# breakout.net
KiCad netlist of a schematic drawn in EAGLE
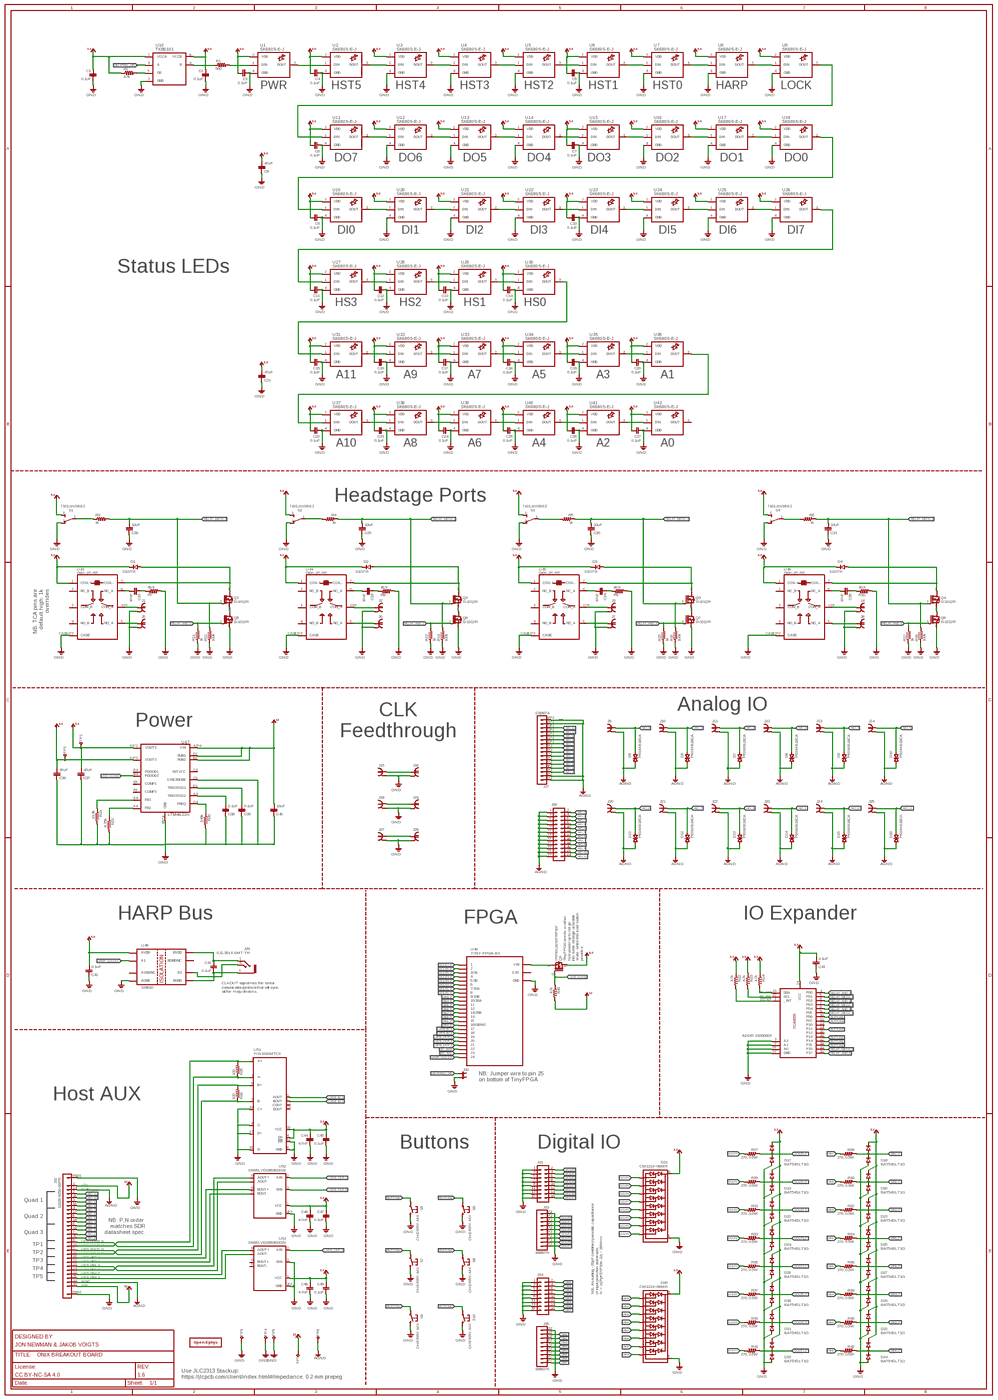
[diagram p0: schematic, sheet 1, overview]
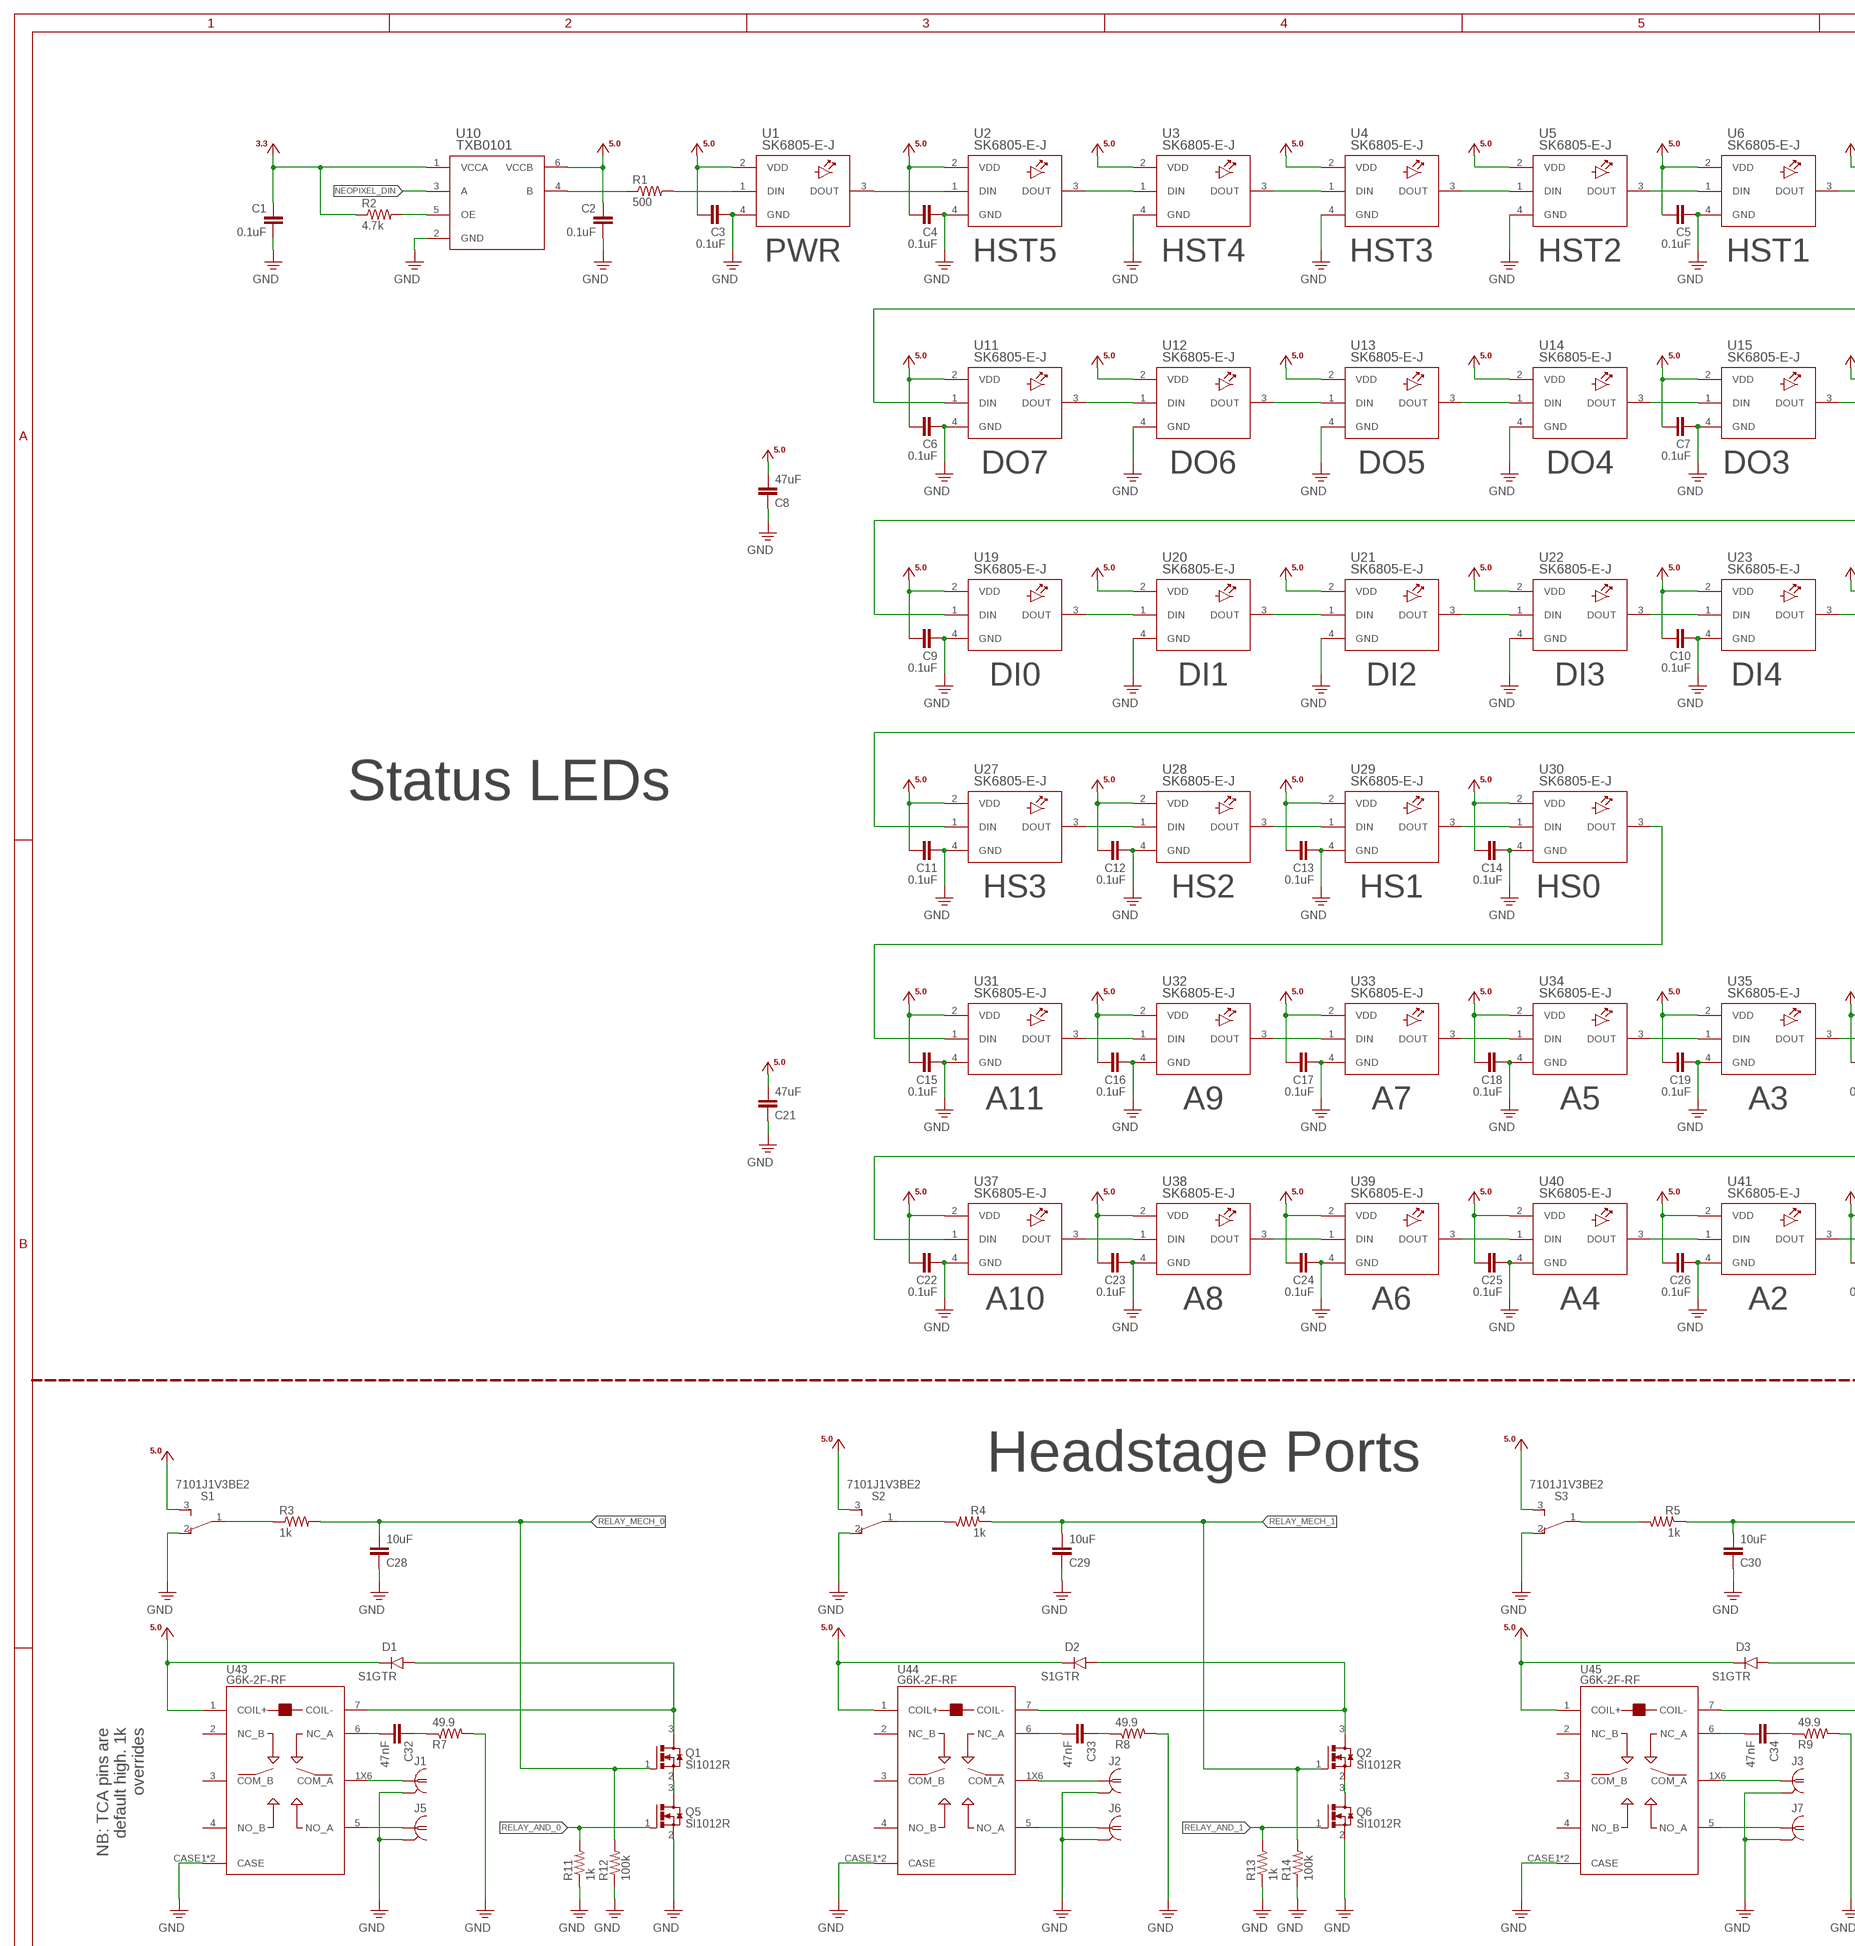
[diagram p1: schematic, sheet 1, part 1 of 4]
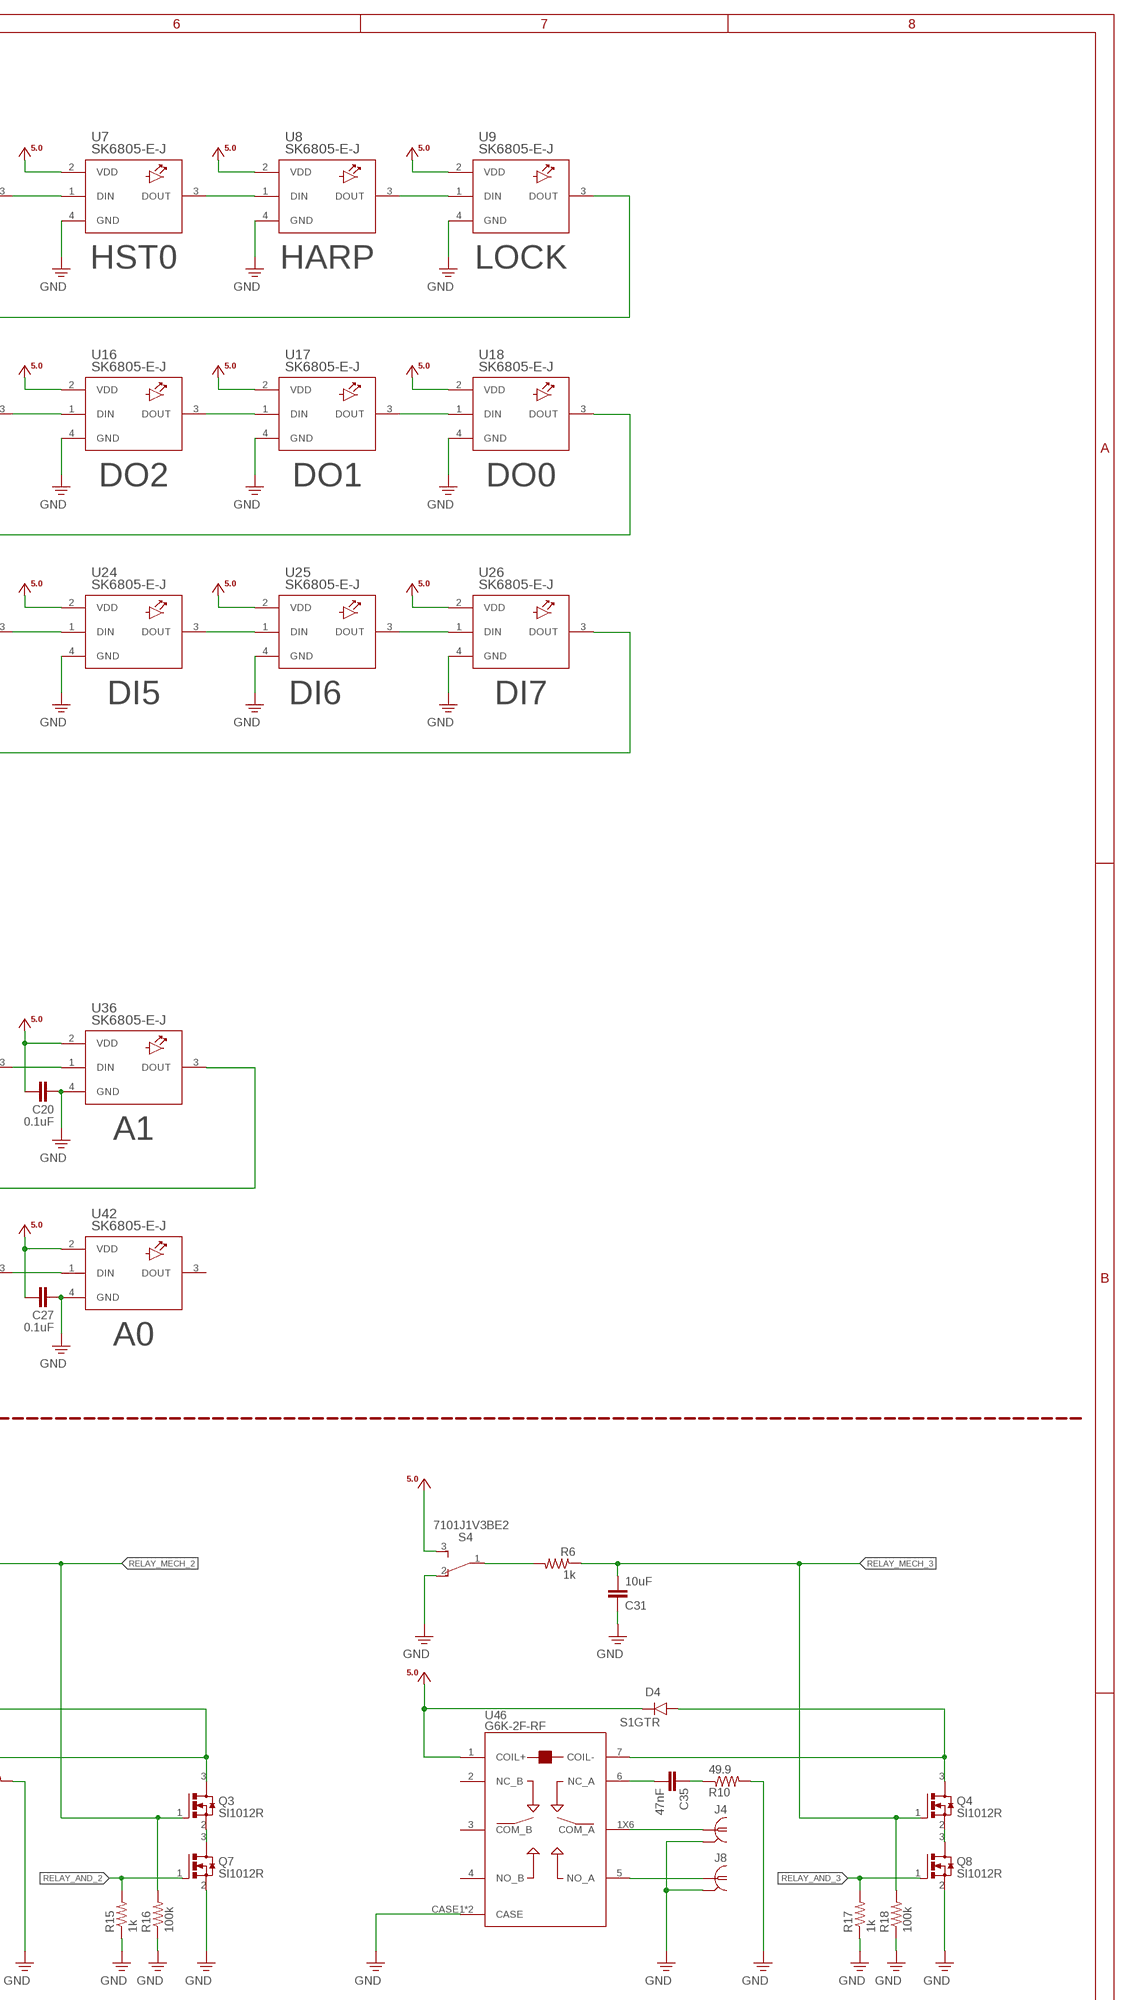
[diagram p2: schematic, sheet 1, part 2 of 4]
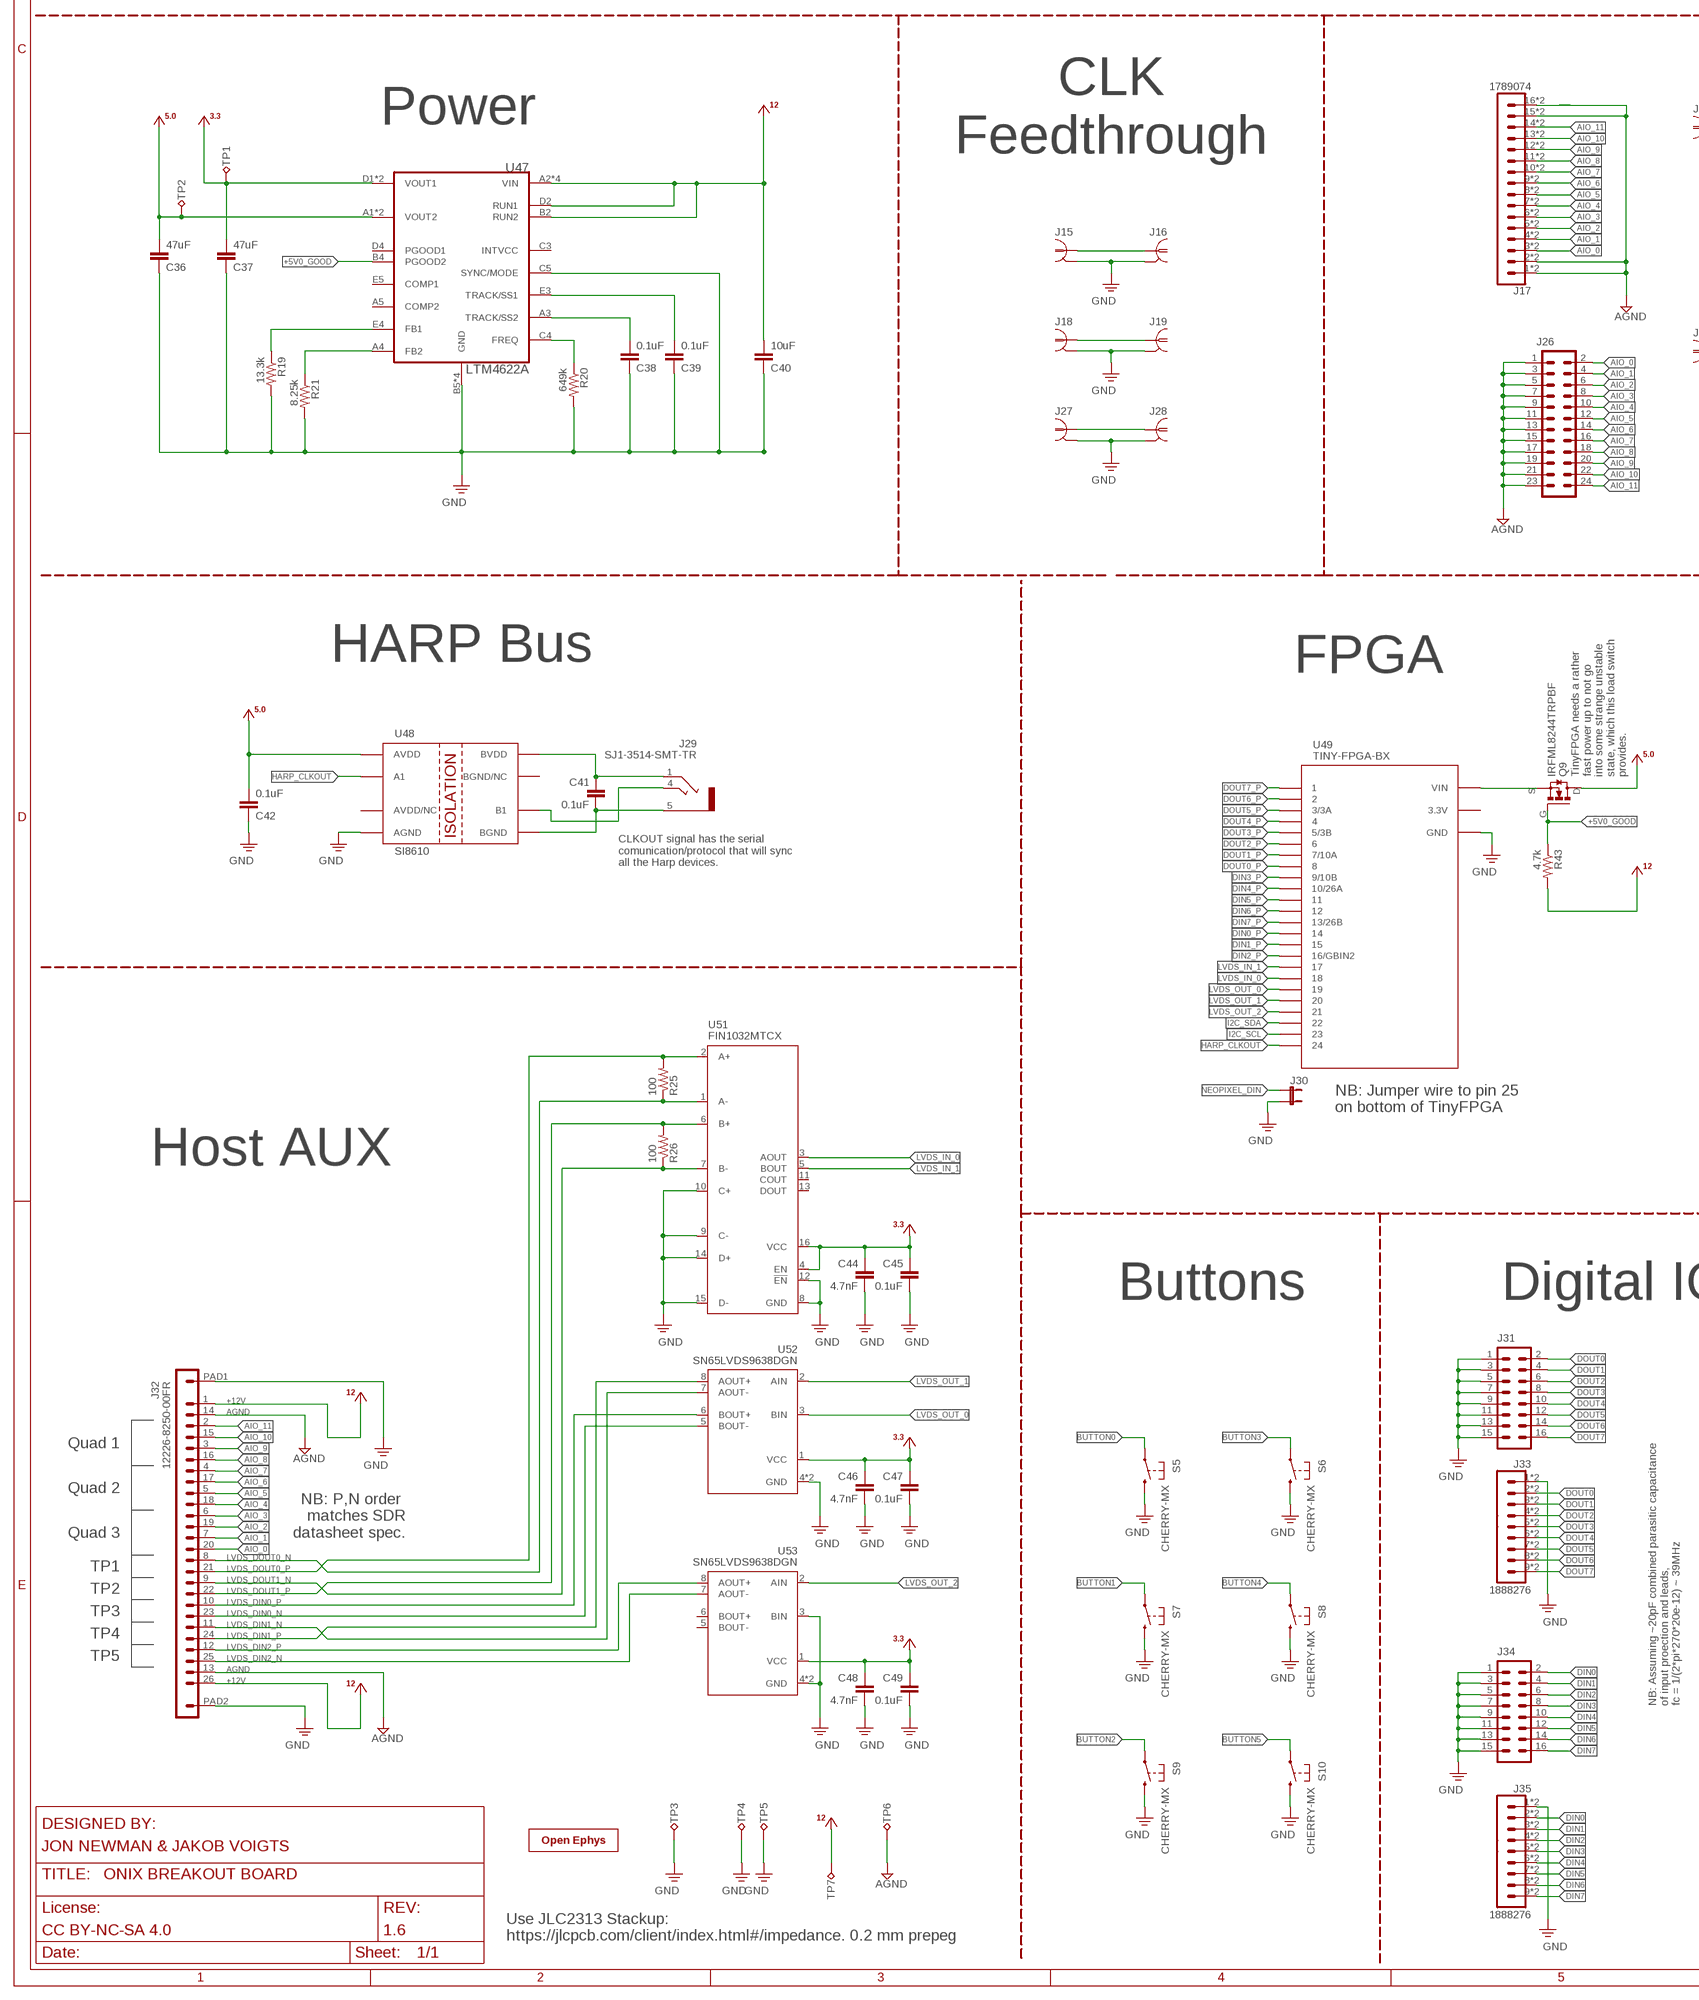
[diagram p3: schematic, sheet 1, part 3 of 4]
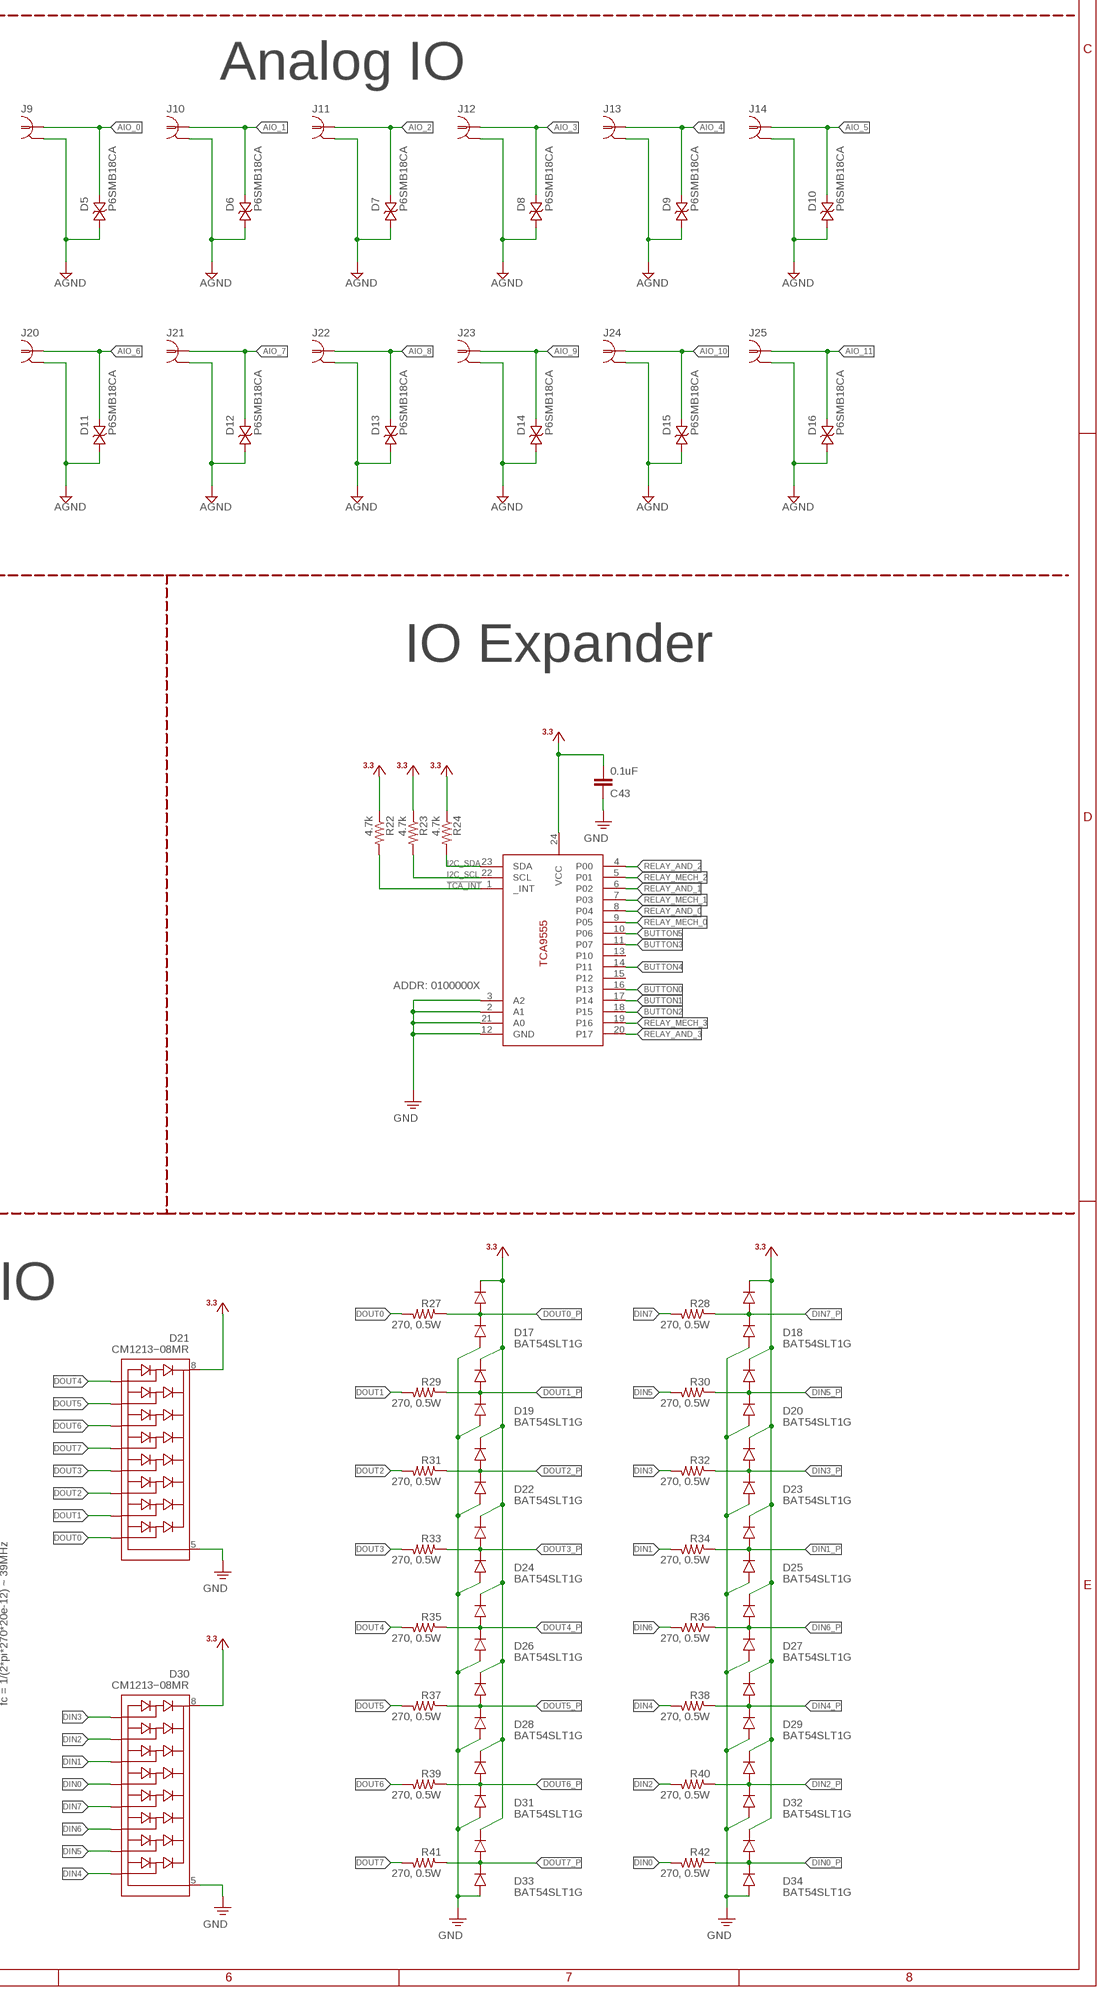
[diagram p4: schematic, sheet 1, part 4 of 4]

(export (version "E")
  (design (tool "Eeschema 10.0.6"))
  (components
    (comp (ref "C1")
      (value "0.1uF")
      (footprint "eagle-import:0402")
      (libsource (lib "eagle-import") (part "C_0402"))
    )
    (comp (ref "C2")
      (value "0.1uF")
      (footprint "eagle-import:0402")
      (libsource (lib "eagle-import") (part "C_0402"))
    )
    (comp (ref "C3")
      (value "0.1uF")
      (footprint "eagle-import:0402")
      (libsource (lib "eagle-import") (part "C_0402"))
    )
    (comp (ref "C4")
      (value "0.1uF")
      (footprint "eagle-import:0402")
      (libsource (lib "eagle-import") (part "C_0402"))
    )
    (comp (ref "C5")
      (value "0.1uF")
      (footprint "eagle-import:0402")
      (libsource (lib "eagle-import") (part "C_0402"))
    )
    (comp (ref "C6")
      (value "0.1uF")
      (footprint "eagle-import:0402")
      (libsource (lib "eagle-import") (part "C_0402"))
    )
    (comp (ref "C7")
      (value "0.1uF")
      (footprint "eagle-import:0402")
      (libsource (lib "eagle-import") (part "C_0402"))
    )
    (comp (ref "C8")
      (value "47uF")
      (footprint "eagle-import:1210")
      (libsource (lib "eagle-import") (part "C_1210"))
    )
    (comp (ref "C9")
      (value "0.1uF")
      (footprint "eagle-import:0402")
      (libsource (lib "eagle-import") (part "C_0402"))
    )
    (comp (ref "C10")
      (value "0.1uF")
      (footprint "eagle-import:0402")
      (libsource (lib "eagle-import") (part "C_0402"))
    )
    (comp (ref "C11")
      (value "0.1uF")
      (footprint "eagle-import:0402")
      (libsource (lib "eagle-import") (part "C_0402"))
    )
    (comp (ref "C12")
      (value "0.1uF")
      (footprint "eagle-import:0402")
      (libsource (lib "eagle-import") (part "C_0402"))
    )
    (comp (ref "C13")
      (value "0.1uF")
      (footprint "eagle-import:0402")
      (libsource (lib "eagle-import") (part "C_0402"))
    )
    (comp (ref "C14")
      (value "0.1uF")
      (footprint "eagle-import:0402")
      (libsource (lib "eagle-import") (part "C_0402"))
    )
    (comp (ref "C15")
      (value "0.1uF")
      (footprint "eagle-import:0402")
      (libsource (lib "eagle-import") (part "C_0402"))
    )
    (comp (ref "C16")
      (value "0.1uF")
      (footprint "eagle-import:0402")
      (libsource (lib "eagle-import") (part "C_0402"))
    )
    (comp (ref "C17")
      (value "0.1uF")
      (footprint "eagle-import:0402")
      (libsource (lib "eagle-import") (part "C_0402"))
    )
    (comp (ref "C18")
      (value "0.1uF")
      (footprint "eagle-import:0402")
      (libsource (lib "eagle-import") (part "C_0402"))
    )
    (comp (ref "C19")
      (value "0.1uF")
      (footprint "eagle-import:0402")
      (libsource (lib "eagle-import") (part "C_0402"))
    )
    (comp (ref "C20")
      (value "0.1uF")
      (footprint "eagle-import:0402")
      (libsource (lib "eagle-import") (part "C_0402"))
    )
    (comp (ref "C21")
      (value "47uF")
      (footprint "eagle-import:1210")
      (libsource (lib "eagle-import") (part "C_1210"))
    )
    (comp (ref "C22")
      (value "0.1uF")
      (footprint "eagle-import:0402")
      (libsource (lib "eagle-import") (part "C_0402"))
    )
    (comp (ref "C23")
      (value "0.1uF")
      (footprint "eagle-import:0402")
      (libsource (lib "eagle-import") (part "C_0402"))
    )
    (comp (ref "C24")
      (value "0.1uF")
      (footprint "eagle-import:0402")
      (libsource (lib "eagle-import") (part "C_0402"))
    )
    (comp (ref "C25")
      (value "0.1uF")
      (footprint "eagle-import:0402")
      (libsource (lib "eagle-import") (part "C_0402"))
    )
    (comp (ref "C26")
      (value "0.1uF")
      (footprint "eagle-import:0402")
      (libsource (lib "eagle-import") (part "C_0402"))
    )
    (comp (ref "C27")
      (value "0.1uF")
      (footprint "eagle-import:0402")
      (libsource (lib "eagle-import") (part "C_0402"))
    )
    (comp (ref "C28")
      (value "10uF")
      (footprint "eagle-import:0805")
      (fields (field (name "PARTNO") "C2012X5R1Cxxxxxxx"))
      (libsource (lib "eagle-import") (part "C_0805"))
    )
    (comp (ref "C29")
      (value "10uF")
      (footprint "eagle-import:0805")
      (fields (field (name "PARTNO") "C2012X5R1Cxxxxxxx"))
      (libsource (lib "eagle-import") (part "C_0805"))
    )
    (comp (ref "C30")
      (value "10uF")
      (footprint "eagle-import:0805")
      (fields (field (name "PARTNO") "C2012X5R1Cxxxxxxx"))
      (libsource (lib "eagle-import") (part "C_0805"))
    )
    (comp (ref "C31")
      (value "10uF")
      (footprint "eagle-import:0805")
      (fields (field (name "PARTNO") "C2012X5R1Cxxxxxxx"))
      (libsource (lib "eagle-import") (part "C_0805"))
    )
    (comp (ref "C32")
      (value "47nF")
      (footprint "eagle-import:0402")
      (libsource (lib "eagle-import") (part "C_0402"))
    )
    (comp (ref "C33")
      (value "47nF")
      (footprint "eagle-import:0402")
      (libsource (lib "eagle-import") (part "C_0402"))
    )
    (comp (ref "C34")
      (value "47nF")
      (footprint "eagle-import:0402")
      (libsource (lib "eagle-import") (part "C_0402"))
    )
    (comp (ref "C35")
      (value "47nF")
      (footprint "eagle-import:0402")
      (libsource (lib "eagle-import") (part "C_0402"))
    )
    (comp (ref "C36")
      (value "47uF")
      (footprint "eagle-import:1210")
      (libsource (lib "eagle-import") (part "C_1210"))
    )
    (comp (ref "C37")
      (value "47uF")
      (footprint "eagle-import:1210")
      (libsource (lib "eagle-import") (part "C_1210"))
    )
    (comp (ref "C38")
      (value "0.1uF")
      (footprint "eagle-import:0402")
      (libsource (lib "eagle-import") (part "C_0402"))
    )
    (comp (ref "C39")
      (value "0.1uF")
      (footprint "eagle-import:0402")
      (libsource (lib "eagle-import") (part "C_0402"))
    )
    (comp (ref "C40")
      (value "10uF")
      (footprint "eagle-import:0805")
      (fields (field (name "PARTNO") "C2012X5R1Cxxxxxxx"))
      (libsource (lib "eagle-import") (part "C_0805"))
    )
    (comp (ref "C41")
      (value "0.1uF")
      (footprint "eagle-import:0402")
      (libsource (lib "eagle-import") (part "C_0402"))
    )
    (comp (ref "C42")
      (value "0.1uF")
      (footprint "eagle-import:0402")
      (libsource (lib "eagle-import") (part "C_0402"))
    )
    (comp (ref "C43")
      (value "0.1uF")
      (footprint "eagle-import:0402")
      (libsource (lib "eagle-import") (part "C_0402"))
    )
    (comp (ref "C44")
      (value "4.7nF")
      (footprint "eagle-import:0402")
      (libsource (lib "eagle-import") (part "C_0402"))
    )
    (comp (ref "C45")
      (value "0.1uF")
      (footprint "eagle-import:0402")
      (libsource (lib "eagle-import") (part "C_0402"))
    )
    (comp (ref "C46")
      (value "4.7nF")
      (footprint "eagle-import:0402")
      (libsource (lib "eagle-import") (part "C_0402"))
    )
    (comp (ref "C47")
      (value "0.1uF")
      (footprint "eagle-import:0402")
      (libsource (lib "eagle-import") (part "C_0402"))
    )
    (comp (ref "C48")
      (value "4.7nF")
      (footprint "eagle-import:0402")
      (libsource (lib "eagle-import") (part "C_0402"))
    )
    (comp (ref "C49")
      (value "0.1uF")
      (footprint "eagle-import:0402")
      (libsource (lib "eagle-import") (part "C_0402"))
    )
    (comp (ref "D1")
      (value "S1GTR")
      (footprint "eagle-import:SMA-DO214AC")
      (libsource (lib "eagle-import") (part "DIODE_S1B-13-F"))
    )
    (comp (ref "D2")
      (value "S1GTR")
      (footprint "eagle-import:SMA-DO214AC")
      (libsource (lib "eagle-import") (part "DIODE_S1B-13-F"))
    )
    (comp (ref "D3")
      (value "S1GTR")
      (footprint "eagle-import:SMA-DO214AC")
      (libsource (lib "eagle-import") (part "DIODE_S1B-13-F"))
    )
    (comp (ref "D4")
      (value "S1GTR")
      (footprint "eagle-import:SMA-DO214AC")
      (libsource (lib "eagle-import") (part "DIODE_S1B-13-F"))
    )
    (comp (ref "D5")
      (value "P6SMB18CA")
      (footprint "eagle-import:SMA-DO214AC")
      (libsource (lib "eagle-import") (part "TVS-DIODE-BI_DO214"))
    )
    (comp (ref "D6")
      (value "P6SMB18CA")
      (footprint "eagle-import:SMA-DO214AC")
      (libsource (lib "eagle-import") (part "TVS-DIODE-BI_DO214"))
    )
    (comp (ref "D7")
      (value "P6SMB18CA")
      (footprint "eagle-import:SMA-DO214AC")
      (libsource (lib "eagle-import") (part "TVS-DIODE-BI_DO214"))
    )
    (comp (ref "D8")
      (value "P6SMB18CA")
      (footprint "eagle-import:SMA-DO214AC")
      (libsource (lib "eagle-import") (part "TVS-DIODE-BI_DO214"))
    )
    (comp (ref "D9")
      (value "P6SMB18CA")
      (footprint "eagle-import:SMA-DO214AC")
      (libsource (lib "eagle-import") (part "TVS-DIODE-BI_DO214"))
    )
    (comp (ref "D10")
      (value "P6SMB18CA")
      (footprint "eagle-import:SMA-DO214AC")
      (libsource (lib "eagle-import") (part "TVS-DIODE-BI_DO214"))
    )
    (comp (ref "D11")
      (value "P6SMB18CA")
      (footprint "eagle-import:SMA-DO214AC")
      (libsource (lib "eagle-import") (part "TVS-DIODE-BI_DO214"))
    )
    (comp (ref "D12")
      (value "P6SMB18CA")
      (footprint "eagle-import:SMA-DO214AC")
      (libsource (lib "eagle-import") (part "TVS-DIODE-BI_DO214"))
    )
    (comp (ref "D13")
      (value "P6SMB18CA")
      (footprint "eagle-import:SMA-DO214AC")
      (libsource (lib "eagle-import") (part "TVS-DIODE-BI_DO214"))
    )
    (comp (ref "D14")
      (value "P6SMB18CA")
      (footprint "eagle-import:SMA-DO214AC")
      (libsource (lib "eagle-import") (part "TVS-DIODE-BI_DO214"))
    )
    (comp (ref "D15")
      (value "P6SMB18CA")
      (footprint "eagle-import:SMA-DO214AC")
      (libsource (lib "eagle-import") (part "TVS-DIODE-BI_DO214"))
    )
    (comp (ref "D16")
      (value "P6SMB18CA")
      (footprint "eagle-import:SMA-DO214AC")
      (libsource (lib "eagle-import") (part "TVS-DIODE-BI_DO214"))
    )
    (comp (ref "D17")
      (value "BAT54SLT1G")
      (footprint "eagle-import:SOT23")
      (libsource (lib "eagle-import") (part "DIODE2_SOT23"))
    )
    (comp (ref "D18")
      (value "BAT54SLT1G")
      (footprint "eagle-import:SOT23")
      (libsource (lib "eagle-import") (part "DIODE2_SOT23"))
    )
    (comp (ref "D19")
      (value "BAT54SLT1G")
      (footprint "eagle-import:SOT23")
      (libsource (lib "eagle-import") (part "DIODE2_SOT23"))
    )
    (comp (ref "D20")
      (value "BAT54SLT1G")
      (footprint "eagle-import:SOT23")
      (libsource (lib "eagle-import") (part "DIODE2_SOT23"))
    )
    (comp (ref "D21")
      (value "CM1213−08MR")
      (footprint "eagle-import:MSOP-10-3X3")
      (libsource (lib "eagle-import") (part "TVS-DIODE-BI-8_MSOP"))
    )
    (comp (ref "D22")
      (value "BAT54SLT1G")
      (footprint "eagle-import:SOT23")
      (libsource (lib "eagle-import") (part "DIODE2_SOT23"))
    )
    (comp (ref "D23")
      (value "BAT54SLT1G")
      (footprint "eagle-import:SOT23")
      (libsource (lib "eagle-import") (part "DIODE2_SOT23"))
    )
    (comp (ref "D24")
      (value "BAT54SLT1G")
      (footprint "eagle-import:SOT23")
      (libsource (lib "eagle-import") (part "DIODE2_SOT23"))
    )
    (comp (ref "D25")
      (value "BAT54SLT1G")
      (footprint "eagle-import:SOT23")
      (libsource (lib "eagle-import") (part "DIODE2_SOT23"))
    )
    (comp (ref "D26")
      (value "BAT54SLT1G")
      (footprint "eagle-import:SOT23")
      (libsource (lib "eagle-import") (part "DIODE2_SOT23"))
    )
    (comp (ref "D27")
      (value "BAT54SLT1G")
      (footprint "eagle-import:SOT23")
      (libsource (lib "eagle-import") (part "DIODE2_SOT23"))
    )
    (comp (ref "D28")
      (value "BAT54SLT1G")
      (footprint "eagle-import:SOT23")
      (libsource (lib "eagle-import") (part "DIODE2_SOT23"))
    )
    (comp (ref "D29")
      (value "BAT54SLT1G")
      (footprint "eagle-import:SOT23")
      (libsource (lib "eagle-import") (part "DIODE2_SOT23"))
    )
    (comp (ref "D30")
      (value "CM1213−08MR")
      (footprint "eagle-import:MSOP-10-3X3")
      (libsource (lib "eagle-import") (part "TVS-DIODE-BI-8_MSOP"))
    )
    (comp (ref "D31")
      (value "BAT54SLT1G")
      (footprint "eagle-import:SOT23")
      (libsource (lib "eagle-import") (part "DIODE2_SOT23"))
    )
    (comp (ref "D32")
      (value "BAT54SLT1G")
      (footprint "eagle-import:SOT23")
      (libsource (lib "eagle-import") (part "DIODE2_SOT23"))
    )
    (comp (ref "D33")
      (value "BAT54SLT1G")
      (footprint "eagle-import:SOT23")
      (libsource (lib "eagle-import") (part "DIODE2_SOT23"))
    )
    (comp (ref "D34")
      (value "BAT54SLT1G")
      (footprint "eagle-import:SOT23")
      (libsource (lib "eagle-import") (part "DIODE2_SOT23"))
    )
    (comp (ref "J1")
      (value "COAX_SMA-VERT")
      (footprint "eagle-import:SMA_JACK_142-0701-201")
      (libsource (lib "eagle-import") (part "COAX_SMA-VERT"))
    )
    (comp (ref "J2")
      (value "COAX_SMA-VERT")
      (footprint "eagle-import:SMA_JACK_142-0701-201")
      (libsource (lib "eagle-import") (part "COAX_SMA-VERT"))
    )
    (comp (ref "J3")
      (value "COAX_SMA-VERT")
      (footprint "eagle-import:SMA_JACK_142-0701-201")
      (libsource (lib "eagle-import") (part "COAX_SMA-VERT"))
    )
    (comp (ref "J4")
      (value "COAX_SMA-VERT")
      (footprint "eagle-import:SMA_JACK_142-0701-201")
      (libsource (lib "eagle-import") (part "COAX_SMA-VERT"))
    )
    (comp (ref "J5")
      (value "COAX_MMCX-THRU")
      (footprint "eagle-import:MMCX-THRU")
      (libsource (lib "eagle-import") (part "COAX_MMCX-THRU"))
    )
    (comp (ref "J6")
      (value "COAX_MMCX-THRU")
      (footprint "eagle-import:MMCX-THRU")
      (libsource (lib "eagle-import") (part "COAX_MMCX-THRU"))
    )
    (comp (ref "J7")
      (value "COAX_MMCX-THRU")
      (footprint "eagle-import:MMCX-THRU")
      (libsource (lib "eagle-import") (part "COAX_MMCX-THRU"))
    )
    (comp (ref "J8")
      (value "COAX_MMCX-THRU")
      (footprint "eagle-import:MMCX-THRU")
      (libsource (lib "eagle-import") (part "COAX_MMCX-THRU"))
    )
    (comp (ref "J9")
      (value "COAX_0731010360")
      (footprint "eagle-import:0731010360")
      (libsource (lib "eagle-import") (part "COAX_0731010360"))
    )
    (comp (ref "J10")
      (value "COAX_0731010360")
      (footprint "eagle-import:0731010360")
      (libsource (lib "eagle-import") (part "COAX_0731010360"))
    )
    (comp (ref "J11")
      (value "COAX_0731010360")
      (footprint "eagle-import:0731010360")
      (libsource (lib "eagle-import") (part "COAX_0731010360"))
    )
    (comp (ref "J12")
      (value "COAX_0731010360")
      (footprint "eagle-import:0731010360")
      (libsource (lib "eagle-import") (part "COAX_0731010360"))
    )
    (comp (ref "J13")
      (value "COAX_0731010360")
      (footprint "eagle-import:0731010360")
      (libsource (lib "eagle-import") (part "COAX_0731010360"))
    )
    (comp (ref "J14")
      (value "COAX_0731010360")
      (footprint "eagle-import:0731010360")
      (libsource (lib "eagle-import") (part "COAX_0731010360"))
    )
    (comp (ref "J15")
      (value "COAX_MMCX-THRU")
      (footprint "eagle-import:MMCX-THRU")
      (libsource (lib "eagle-import") (part "COAX_MMCX-THRU"))
    )
    (comp (ref "J16")
      (value "COAX_SMA-VERT")
      (footprint "eagle-import:SMA_JACK_142-0701-201")
      (libsource (lib "eagle-import") (part "COAX_SMA-VERT"))
    )
    (comp (ref "J17")
      (value "1789074")
      (footprint "eagle-import:SCREW16-2")
      (libsource (lib "eagle-import") (part "PINHD-1X16"))
    )
    (comp (ref "J18")
      (value "COAX_MMCX-THRU")
      (footprint "eagle-import:MMCX-THRU")
      (libsource (lib "eagle-import") (part "COAX_MMCX-THRU"))
    )
    (comp (ref "J19")
      (value "COAX_SMA-VERT")
      (footprint "eagle-import:SMA_JACK_142-0701-201")
      (libsource (lib "eagle-import") (part "COAX_SMA-VERT"))
    )
    (comp (ref "J20")
      (value "COAX_0731010360")
      (footprint "eagle-import:0731010360")
      (libsource (lib "eagle-import") (part "COAX_0731010360"))
    )
    (comp (ref "J21")
      (value "COAX_0731010360")
      (footprint "eagle-import:0731010360")
      (libsource (lib "eagle-import") (part "COAX_0731010360"))
    )
    (comp (ref "J22")
      (value "COAX_0731010360")
      (footprint "eagle-import:0731010360")
      (libsource (lib "eagle-import") (part "COAX_0731010360"))
    )
    (comp (ref "J23")
      (value "COAX_0731010360")
      (footprint "eagle-import:0731010360")
      (libsource (lib "eagle-import") (part "COAX_0731010360"))
    )
    (comp (ref "J24")
      (value "COAX_0731010360")
      (footprint "eagle-import:0731010360")
      (libsource (lib "eagle-import") (part "COAX_0731010360"))
    )
    (comp (ref "J25")
      (value "COAX_0731010360")
      (footprint "eagle-import:0731010360")
      (libsource (lib "eagle-import") (part "COAX_0731010360"))
    )
    (comp (ref "J26")
      (value "69168-124HLF")
      (footprint "eagle-import:2X12-BIG")
      (libsource (lib "eagle-import") (part "PINHD-2X12_0.1{dblquote}"))
    )
    (comp (ref "J27")
      (value "COAX_MMCX-THRU")
      (footprint "eagle-import:MMCX-THRU")
      (libsource (lib "eagle-import") (part "COAX_MMCX-THRU"))
    )
    (comp (ref "J28")
      (value "COAX_SMA-VERT")
      (footprint "eagle-import:SMA_JACK_142-0701-201")
      (libsource (lib "eagle-import") (part "COAX_SMA-VERT"))
    )
    (comp (ref "J29")
      (value "SJ1-3514-SMT-TR")
      (footprint "eagle-import:35RASMT2BHNTRX")
      (libsource (lib "eagle-import") (part "STEREO_JACK"))
    )
    (comp (ref "J30")
      (value "JP2E_THRU-HOLE")
      (footprint "eagle-import:JP2")
      (libsource (lib "eagle-import") (part "JP2E_THRU-HOLE"))
    )
    (comp (ref "J31")
      (value "69168-116HLF")
      (footprint "eagle-import:2X08-BIG")
      (libsource (lib "eagle-import") (part "PINHD-2X8_THRU"))
    )
    (comp (ref "J32")
      (value "12226-8250-00FR")
      (footprint "eagle-import:12226-82X0-00XX")
      (libsource (lib "eagle-import") (part "PINHD-1X26_122"))
    )
    (comp (ref "J33")
      (value "1888276")
      (footprint "eagle-import:SCREW9-2")
      (libsource (lib "eagle-import") (part "PINHD-1X9_SCREW2"))
    )
    (comp (ref "J34")
      (value "69168-116HLF")
      (footprint "eagle-import:2X08-BIG")
      (libsource (lib "eagle-import") (part "PINHD-2X8_THRU"))
    )
    (comp (ref "J35")
      (value "1888276")
      (footprint "eagle-import:SCREW9-2")
      (libsource (lib "eagle-import") (part "PINHD-1X9_SCREW2"))
    )
    (comp (ref "Q1")
      (value "SI1012R")
      (footprint "eagle-import:SC75")
      (libsource (lib "eagle-import") (part "N-MOSFET_SC75-GSD"))
    )
    (comp (ref "Q2")
      (value "SI1012R")
      (footprint "eagle-import:SC75")
      (libsource (lib "eagle-import") (part "N-MOSFET_SC75-GSD"))
    )
    (comp (ref "Q3")
      (value "SI1012R")
      (footprint "eagle-import:SC75")
      (libsource (lib "eagle-import") (part "N-MOSFET_SC75-GSD"))
    )
    (comp (ref "Q4")
      (value "SI1012R")
      (footprint "eagle-import:SC75")
      (libsource (lib "eagle-import") (part "N-MOSFET_SC75-GSD"))
    )
    (comp (ref "Q5")
      (value "SI1012R")
      (footprint "eagle-import:SC75")
      (libsource (lib "eagle-import") (part "N-MOSFET_SC75-GSD"))
    )
    (comp (ref "Q6")
      (value "SI1012R")
      (footprint "eagle-import:SC75")
      (libsource (lib "eagle-import") (part "N-MOSFET_SC75-GSD"))
    )
    (comp (ref "Q7")
      (value "SI1012R")
      (footprint "eagle-import:SC75")
      (libsource (lib "eagle-import") (part "N-MOSFET_SC75-GSD"))
    )
    (comp (ref "Q8")
      (value "SI1012R")
      (footprint "eagle-import:SC75")
      (libsource (lib "eagle-import") (part "N-MOSFET_SC75-GSD"))
    )
    (comp (ref "Q9")
      (value "IRFML8244TRPBF")
      (footprint "eagle-import:SOT23-GSD")
      (libsource (lib "eagle-import") (part "N-MOSFET_SOT23-GSD"))
    )
    (comp (ref "R1")
      (value "500")
      (footprint "eagle-import:0402")
      (libsource (lib "eagle-import") (part "R_0402"))
    )
    (comp (ref "R2")
      (value "4.7k")
      (footprint "eagle-import:0402")
      (libsource (lib "eagle-import") (part "R_0402"))
    )
    (comp (ref "R3")
      (value "1k")
      (footprint "eagle-import:0402")
      (libsource (lib "eagle-import") (part "R_0402"))
    )
    (comp (ref "R4")
      (value "1k")
      (footprint "eagle-import:0402")
      (libsource (lib "eagle-import") (part "R_0402"))
    )
    (comp (ref "R5")
      (value "1k")
      (footprint "eagle-import:0402")
      (libsource (lib "eagle-import") (part "R_0402"))
    )
    (comp (ref "R6")
      (value "1k")
      (footprint "eagle-import:0402")
      (libsource (lib "eagle-import") (part "R_0402"))
    )
    (comp (ref "R7")
      (value "49.9")
      (footprint "eagle-import:0402")
      (libsource (lib "eagle-import") (part "R_0402"))
    )
    (comp (ref "R8")
      (value "49.9")
      (footprint "eagle-import:0402")
      (libsource (lib "eagle-import") (part "R_0402"))
    )
    (comp (ref "R9")
      (value "49.9")
      (footprint "eagle-import:0402")
      (libsource (lib "eagle-import") (part "R_0402"))
    )
    (comp (ref "R10")
      (value "49.9")
      (footprint "eagle-import:0402")
      (libsource (lib "eagle-import") (part "R_0402"))
    )
    (comp (ref "R11")
      (value "1k")
      (footprint "eagle-import:0402")
      (libsource (lib "eagle-import") (part "R_0402"))
    )
    (comp (ref "R12")
      (value "100k")
      (footprint "eagle-import:0402")
      (libsource (lib "eagle-import") (part "R_0402"))
    )
    (comp (ref "R13")
      (value "1k")
      (footprint "eagle-import:0402")
      (libsource (lib "eagle-import") (part "R_0402"))
    )
    (comp (ref "R14")
      (value "100k")
      (footprint "eagle-import:0402")
      (libsource (lib "eagle-import") (part "R_0402"))
    )
    (comp (ref "R15")
      (value "1k")
      (footprint "eagle-import:0402")
      (libsource (lib "eagle-import") (part "R_0402"))
    )
    (comp (ref "R16")
      (value "100k")
      (footprint "eagle-import:0402")
      (libsource (lib "eagle-import") (part "R_0402"))
    )
    (comp (ref "R17")
      (value "1k")
      (footprint "eagle-import:0402")
      (libsource (lib "eagle-import") (part "R_0402"))
    )
    (comp (ref "R18")
      (value "100k")
      (footprint "eagle-import:0402")
      (libsource (lib "eagle-import") (part "R_0402"))
    )
    (comp (ref "R19")
      (value "13.3k")
      (footprint "eagle-import:0402")
      (libsource (lib "eagle-import") (part "R_0402"))
    )
    (comp (ref "R20")
      (value "649k")
      (footprint "eagle-import:0402")
      (libsource (lib "eagle-import") (part "R_0402"))
    )
    (comp (ref "R21")
      (value "8.25k")
      (footprint "eagle-import:0402")
      (libsource (lib "eagle-import") (part "R_0402"))
    )
    (comp (ref "R22")
      (value "4.7k")
      (footprint "eagle-import:0402")
      (libsource (lib "eagle-import") (part "R_0402"))
    )
    (comp (ref "R23")
      (value "4.7k")
      (footprint "eagle-import:0402")
      (libsource (lib "eagle-import") (part "R_0402"))
    )
    (comp (ref "R24")
      (value "4.7k")
      (footprint "eagle-import:0402")
      (libsource (lib "eagle-import") (part "R_0402"))
    )
    (comp (ref "R25")
      (value "100")
      (footprint "eagle-import:0402")
      (libsource (lib "eagle-import") (part "R_0402"))
    )
    (comp (ref "R26")
      (value "100")
      (footprint "eagle-import:0402")
      (libsource (lib "eagle-import") (part "R_0402"))
    )
    (comp (ref "R27")
      (value "270, 0.5W")
      (footprint "eagle-import:0805")
      (libsource (lib "eagle-import") (part "R_0805"))
    )
    (comp (ref "R28")
      (value "270, 0.5W")
      (footprint "eagle-import:0805")
      (libsource (lib "eagle-import") (part "R_0805"))
    )
    (comp (ref "R29")
      (value "270, 0.5W")
      (footprint "eagle-import:0805")
      (libsource (lib "eagle-import") (part "R_0805"))
    )
    (comp (ref "R30")
      (value "270, 0.5W")
      (footprint "eagle-import:0805")
      (libsource (lib "eagle-import") (part "R_0805"))
    )
    (comp (ref "R31")
      (value "270, 0.5W")
      (footprint "eagle-import:0805")
      (libsource (lib "eagle-import") (part "R_0805"))
    )
    (comp (ref "R32")
      (value "270, 0.5W")
      (footprint "eagle-import:0805")
      (libsource (lib "eagle-import") (part "R_0805"))
    )
    (comp (ref "R33")
      (value "270, 0.5W")
      (footprint "eagle-import:0805")
      (libsource (lib "eagle-import") (part "R_0805"))
    )
    (comp (ref "R34")
      (value "270, 0.5W")
      (footprint "eagle-import:0805")
      (libsource (lib "eagle-import") (part "R_0805"))
    )
    (comp (ref "R35")
      (value "270, 0.5W")
      (footprint "eagle-import:0805")
      (libsource (lib "eagle-import") (part "R_0805"))
    )
    (comp (ref "R36")
      (value "270, 0.5W")
      (footprint "eagle-import:0805")
      (libsource (lib "eagle-import") (part "R_0805"))
    )
    (comp (ref "R37")
      (value "270, 0.5W")
      (footprint "eagle-import:0805")
      (libsource (lib "eagle-import") (part "R_0805"))
    )
    (comp (ref "R38")
      (value "270, 0.5W")
      (footprint "eagle-import:0805")
      (libsource (lib "eagle-import") (part "R_0805"))
    )
    (comp (ref "R39")
      (value "270, 0.5W")
      (footprint "eagle-import:0805")
      (libsource (lib "eagle-import") (part "R_0805"))
    )
    (comp (ref "R40")
      (value "270, 0.5W")
      (footprint "eagle-import:0805")
      (libsource (lib "eagle-import") (part "R_0805"))
    )
    (comp (ref "R41")
      (value "270, 0.5W")
      (footprint "eagle-import:0805")
      (libsource (lib "eagle-import") (part "R_0805"))
    )
    (comp (ref "R42")
      (value "270, 0.5W")
      (footprint "eagle-import:0805")
      (libsource (lib "eagle-import") (part "R_0805"))
    )
    (comp (ref "R43")
      (value "4.7k")
      (footprint "eagle-import:0402")
      (libsource (lib "eagle-import") (part "R_0402"))
    )
    (comp (ref "S1")
      (value "7101J1V3BE2")
      (footprint "eagle-import:CK_7101J1V3QE2")
      (libsource (lib "eagle-import") (part "SPDT_CK-710"))
    )
    (comp (ref "S2")
      (value "7101J1V3BE2")
      (footprint "eagle-import:CK_7101J1V3QE2")
      (libsource (lib "eagle-import") (part "SPDT_CK-710"))
    )
    (comp (ref "S3")
      (value "7101J1V3BE2")
      (footprint "eagle-import:CK_7101J1V3QE2")
      (libsource (lib "eagle-import") (part "SPDT_CK-710"))
    )
    (comp (ref "S4")
      (value "7101J1V3BE2")
      (footprint "eagle-import:CK_7101J1V3QE2")
      (libsource (lib "eagle-import") (part "SPDT_CK-710"))
    )
    (comp (ref "S5")
      (value "CHERRY-MX")
      (footprint "eagle-import:CHERRY-MX")
      (libsource (lib "eagle-import") (part "SPST_TACT2_CHERRY-MX"))
    )
    (comp (ref "S6")
      (value "CHERRY-MX")
      (footprint "eagle-import:CHERRY-MX")
      (libsource (lib "eagle-import") (part "SPST_TACT2_CHERRY-MX"))
    )
    (comp (ref "S7")
      (value "CHERRY-MX")
      (footprint "eagle-import:CHERRY-MX")
      (libsource (lib "eagle-import") (part "SPST_TACT2_CHERRY-MX"))
    )
    (comp (ref "S8")
      (value "CHERRY-MX")
      (footprint "eagle-import:CHERRY-MX")
      (libsource (lib "eagle-import") (part "SPST_TACT2_CHERRY-MX"))
    )
    (comp (ref "S9")
      (value "CHERRY-MX")
      (footprint "eagle-import:CHERRY-MX")
      (libsource (lib "eagle-import") (part "SPST_TACT2_CHERRY-MX"))
    )
    (comp (ref "S10")
      (value "CHERRY-MX")
      (footprint "eagle-import:CHERRY-MX")
      (libsource (lib "eagle-import") (part "SPST_TACT2_CHERRY-MX"))
    )
    (comp (ref "TP1")
      (value "TPTP19R")
      (footprint "eagle-import:TP19R")
      (libsource (lib "eagle-import") (part "TPTP19R"))
    )
    (comp (ref "TP2")
      (value "TPTP19R")
      (footprint "eagle-import:TP19R")
      (libsource (lib "eagle-import") (part "TPTP19R"))
    )
    (comp (ref "TP3")
      (value "TP_2MM")
      (footprint "eagle-import:TESTPOINT_2MM")
      (libsource (lib "eagle-import") (part "TP_2MM"))
    )
    (comp (ref "TP4")
      (value "TP_2MM")
      (footprint "eagle-import:TESTPOINT_2MM")
      (libsource (lib "eagle-import") (part "TP_2MM"))
    )
    (comp (ref "TP5")
      (value "TP_2MM")
      (footprint "eagle-import:TESTPOINT_2MM")
      (libsource (lib "eagle-import") (part "TP_2MM"))
    )
    (comp (ref "TP6")
      (value "TP_2MM")
      (footprint "eagle-import:TESTPOINT_2MM")
      (libsource (lib "eagle-import") (part "TP_2MM"))
    )
    (comp (ref "TP7")
      (value "TP_2MM")
      (footprint "eagle-import:TESTPOINT_2MM")
      (libsource (lib "eagle-import") (part "TP_2MM"))
    )
    (comp (ref "U1")
      (value "SK6805-E-J")
      (footprint "eagle-import:NEOPIXEL-1.5X1.5")
      (libsource (lib "eagle-import") (part "NEOPIXEL_1.5X1.5"))
    )
    (comp (ref "U2")
      (value "SK6805-E-J")
      (footprint "eagle-import:NEOPIXEL-1.5X1.5")
      (libsource (lib "eagle-import") (part "NEOPIXEL_1.5X1.5"))
    )
    (comp (ref "U3")
      (value "SK6805-E-J")
      (footprint "eagle-import:NEOPIXEL-1.5X1.5")
      (libsource (lib "eagle-import") (part "NEOPIXEL_1.5X1.5"))
    )
    (comp (ref "U4")
      (value "SK6805-E-J")
      (footprint "eagle-import:NEOPIXEL-1.5X1.5")
      (libsource (lib "eagle-import") (part "NEOPIXEL_1.5X1.5"))
    )
    (comp (ref "U5")
      (value "SK6805-E-J")
      (footprint "eagle-import:NEOPIXEL-1.5X1.5")
      (libsource (lib "eagle-import") (part "NEOPIXEL_1.5X1.5"))
    )
    (comp (ref "U6")
      (value "SK6805-E-J")
      (footprint "eagle-import:NEOPIXEL-1.5X1.5")
      (libsource (lib "eagle-import") (part "NEOPIXEL_1.5X1.5"))
    )
    (comp (ref "U7")
      (value "SK6805-E-J")
      (footprint "eagle-import:NEOPIXEL-1.5X1.5")
      (libsource (lib "eagle-import") (part "NEOPIXEL_1.5X1.5"))
    )
    (comp (ref "U8")
      (value "SK6805-E-J")
      (footprint "eagle-import:NEOPIXEL-1.5X1.5")
      (libsource (lib "eagle-import") (part "NEOPIXEL_1.5X1.5"))
    )
    (comp (ref "U9")
      (value "SK6805-E-J")
      (footprint "eagle-import:NEOPIXEL-1.5X1.5")
      (libsource (lib "eagle-import") (part "NEOPIXEL_1.5X1.5"))
    )
    (comp (ref "U10")
      (value "TXB0101")
      (footprint "eagle-import:SOT23-6")
      (libsource (lib "eagle-import") (part "LEVEL_SHIFTER_SOT23"))
    )
    (comp (ref "U11")
      (value "SK6805-E-J")
      (footprint "eagle-import:NEOPIXEL-1.5X1.5")
      (libsource (lib "eagle-import") (part "NEOPIXEL_1.5X1.5"))
    )
    (comp (ref "U12")
      (value "SK6805-E-J")
      (footprint "eagle-import:NEOPIXEL-1.5X1.5")
      (libsource (lib "eagle-import") (part "NEOPIXEL_1.5X1.5"))
    )
    (comp (ref "U13")
      (value "SK6805-E-J")
      (footprint "eagle-import:NEOPIXEL-1.5X1.5")
      (libsource (lib "eagle-import") (part "NEOPIXEL_1.5X1.5"))
    )
    (comp (ref "U14")
      (value "SK6805-E-J")
      (footprint "eagle-import:NEOPIXEL-1.5X1.5")
      (libsource (lib "eagle-import") (part "NEOPIXEL_1.5X1.5"))
    )
    (comp (ref "U15")
      (value "SK6805-E-J")
      (footprint "eagle-import:NEOPIXEL-1.5X1.5")
      (libsource (lib "eagle-import") (part "NEOPIXEL_1.5X1.5"))
    )
    (comp (ref "U16")
      (value "SK6805-E-J")
      (footprint "eagle-import:NEOPIXEL-1.5X1.5")
      (libsource (lib "eagle-import") (part "NEOPIXEL_1.5X1.5"))
    )
    (comp (ref "U17")
      (value "SK6805-E-J")
      (footprint "eagle-import:NEOPIXEL-1.5X1.5")
      (libsource (lib "eagle-import") (part "NEOPIXEL_1.5X1.5"))
    )
    (comp (ref "U18")
      (value "SK6805-E-J")
      (footprint "eagle-import:NEOPIXEL-1.5X1.5")
      (libsource (lib "eagle-import") (part "NEOPIXEL_1.5X1.5"))
    )
    (comp (ref "U19")
      (value "SK6805-E-J")
      (footprint "eagle-import:NEOPIXEL-1.5X1.5")
      (libsource (lib "eagle-import") (part "NEOPIXEL_1.5X1.5"))
    )
    (comp (ref "U20")
      (value "SK6805-E-J")
      (footprint "eagle-import:NEOPIXEL-1.5X1.5")
      (libsource (lib "eagle-import") (part "NEOPIXEL_1.5X1.5"))
    )
    (comp (ref "U21")
      (value "SK6805-E-J")
      (footprint "eagle-import:NEOPIXEL-1.5X1.5")
      (libsource (lib "eagle-import") (part "NEOPIXEL_1.5X1.5"))
    )
    (comp (ref "U22")
      (value "SK6805-E-J")
      (footprint "eagle-import:NEOPIXEL-1.5X1.5")
      (libsource (lib "eagle-import") (part "NEOPIXEL_1.5X1.5"))
    )
    (comp (ref "U23")
      (value "SK6805-E-J")
      (footprint "eagle-import:NEOPIXEL-1.5X1.5")
      (libsource (lib "eagle-import") (part "NEOPIXEL_1.5X1.5"))
    )
    (comp (ref "U24")
      (value "SK6805-E-J")
      (footprint "eagle-import:NEOPIXEL-1.5X1.5")
      (libsource (lib "eagle-import") (part "NEOPIXEL_1.5X1.5"))
    )
    (comp (ref "U25")
      (value "SK6805-E-J")
      (footprint "eagle-import:NEOPIXEL-1.5X1.5")
      (libsource (lib "eagle-import") (part "NEOPIXEL_1.5X1.5"))
    )
    (comp (ref "U26")
      (value "SK6805-E-J")
      (footprint "eagle-import:NEOPIXEL-1.5X1.5")
      (libsource (lib "eagle-import") (part "NEOPIXEL_1.5X1.5"))
    )
    (comp (ref "U27")
      (value "SK6805-E-J")
      (footprint "eagle-import:NEOPIXEL-1.5X1.5")
      (libsource (lib "eagle-import") (part "NEOPIXEL_1.5X1.5"))
    )
    (comp (ref "U28")
      (value "SK6805-E-J")
      (footprint "eagle-import:NEOPIXEL-1.5X1.5")
      (libsource (lib "eagle-import") (part "NEOPIXEL_1.5X1.5"))
    )
    (comp (ref "U29")
      (value "SK6805-E-J")
      (footprint "eagle-import:NEOPIXEL-1.5X1.5")
      (libsource (lib "eagle-import") (part "NEOPIXEL_1.5X1.5"))
    )
    (comp (ref "U30")
      (value "SK6805-E-J")
      (footprint "eagle-import:NEOPIXEL-1.5X1.5")
      (libsource (lib "eagle-import") (part "NEOPIXEL_1.5X1.5"))
    )
    (comp (ref "U31")
      (value "SK6805-E-J")
      (footprint "eagle-import:NEOPIXEL-1.5X1.5")
      (libsource (lib "eagle-import") (part "NEOPIXEL_1.5X1.5"))
    )
    (comp (ref "U32")
      (value "SK6805-E-J")
      (footprint "eagle-import:NEOPIXEL-1.5X1.5")
      (libsource (lib "eagle-import") (part "NEOPIXEL_1.5X1.5"))
    )
    (comp (ref "U33")
      (value "SK6805-E-J")
      (footprint "eagle-import:NEOPIXEL-1.5X1.5")
      (libsource (lib "eagle-import") (part "NEOPIXEL_1.5X1.5"))
    )
    (comp (ref "U34")
      (value "SK6805-E-J")
      (footprint "eagle-import:NEOPIXEL-1.5X1.5")
      (libsource (lib "eagle-import") (part "NEOPIXEL_1.5X1.5"))
    )
    (comp (ref "U35")
      (value "SK6805-E-J")
      (footprint "eagle-import:NEOPIXEL-1.5X1.5")
      (libsource (lib "eagle-import") (part "NEOPIXEL_1.5X1.5"))
    )
    (comp (ref "U36")
      (value "SK6805-E-J")
      (footprint "eagle-import:NEOPIXEL-1.5X1.5")
      (libsource (lib "eagle-import") (part "NEOPIXEL_1.5X1.5"))
    )
    (comp (ref "U37")
      (value "SK6805-E-J")
      (footprint "eagle-import:NEOPIXEL-1.5X1.5")
      (libsource (lib "eagle-import") (part "NEOPIXEL_1.5X1.5"))
    )
    (comp (ref "U38")
      (value "SK6805-E-J")
      (footprint "eagle-import:NEOPIXEL-1.5X1.5")
      (libsource (lib "eagle-import") (part "NEOPIXEL_1.5X1.5"))
    )
    (comp (ref "U39")
      (value "SK6805-E-J")
      (footprint "eagle-import:NEOPIXEL-1.5X1.5")
      (libsource (lib "eagle-import") (part "NEOPIXEL_1.5X1.5"))
    )
    (comp (ref "U40")
      (value "SK6805-E-J")
      (footprint "eagle-import:NEOPIXEL-1.5X1.5")
      (libsource (lib "eagle-import") (part "NEOPIXEL_1.5X1.5"))
    )
    (comp (ref "U41")
      (value "SK6805-E-J")
      (footprint "eagle-import:NEOPIXEL-1.5X1.5")
      (libsource (lib "eagle-import") (part "NEOPIXEL_1.5X1.5"))
    )
    (comp (ref "U42")
      (value "SK6805-E-J")
      (footprint "eagle-import:NEOPIXEL-1.5X1.5")
      (libsource (lib "eagle-import") (part "NEOPIXEL_1.5X1.5"))
    )
    (comp (ref "U43")
      (value "G6K-2F-RF")
      (footprint "eagle-import:G6KU-2F-RF")
      (libsource (lib "eagle-import") (part "G6KU-2F-RF-TR09DC5"))
    )
    (comp (ref "U44")
      (value "G6K-2F-RF")
      (footprint "eagle-import:G6KU-2F-RF")
      (libsource (lib "eagle-import") (part "G6KU-2F-RF-TR09DC5"))
    )
    (comp (ref "U45")
      (value "G6K-2F-RF")
      (footprint "eagle-import:G6KU-2F-RF")
      (libsource (lib "eagle-import") (part "G6KU-2F-RF-TR09DC5"))
    )
    (comp (ref "U46")
      (value "G6K-2F-RF")
      (footprint "eagle-import:G6KU-2F-RF")
      (libsource (lib "eagle-import") (part "G6KU-2F-RF-TR09DC5"))
    )
    (comp (ref "U47")
      (value "LTM4622A")
      (footprint "eagle-import:BGA_5X5_625X625")
      (libsource (lib "eagle-import") (part "LTM4622_BGA"))
    )
    (comp (ref "U48")
      (value "SI8610")
      (footprint "eagle-import:SO-08")
      (libsource (lib "eagle-import") (part "SI8610"))
    )
    (comp (ref "U49")
      (value "TINY-FPGA-BX")
      (footprint "eagle-import:TINY-FPGA-BX_BASIC")
      (libsource (lib "eagle-import") (part "TINY-FPGA-BX_BASIC"))
    )
    (comp (ref "U50")
      (value "TCA9555")
      (footprint "eagle-import:TSSOP-24")
      (libsource (lib "eagle-import") (part "TCA9555"))
    )
    (comp (ref "U51")
      (value "FIN1032MTCX")
      (footprint "eagle-import:TSSOP-16")
      (libsource (lib "eagle-import") (part "LVDS_RECEIVER_QUAD_TSSOP"))
    )
    (comp (ref "U52")
      (value "SN65LVDS9638DGN")
      (footprint "eagle-import:MSOP-8-PAD-3X3")
      (libsource (lib "eagle-import") (part "LVDS_DRIVER_DUAL_MSOP"))
    )
    (comp (ref "U53")
      (value "SN65LVDS9638DGN")
      (footprint "eagle-import:MSOP-8-PAD-3X3")
      (libsource (lib "eagle-import") (part "LVDS_DRIVER_DUAL_MSOP"))
    )
    (comp (ref "X")
      (value "OE-LOGO_28X20")
      (footprint "eagle-import:OE-LOGO-28X20")
      (libsource (lib "eagle-import") (part "OE-LOGO_28X20"))
    )
  )
  (nets
    (net (code "1") (name "+3V3") (class "Default")
      (node (ref "C1") (pin "1") (pinfunction "1_1") (pintype "passive"))
      (node (ref "C37") (pin "2") (pinfunction "2_2") (pintype "passive"))
      (node (ref "C43") (pin "2") (pinfunction "2_2") (pintype "passive"))
      (node (ref "C44") (pin "1") (pinfunction "1_1") (pintype "passive"))
      (node (ref "C45") (pin "1") (pinfunction "1_1") (pintype "passive"))
      (node (ref "C46") (pin "1") (pinfunction "1_1") (pintype "passive"))
      (node (ref "C47") (pin "1") (pinfunction "1_1") (pintype "passive"))
      (node (ref "C48") (pin "1") (pinfunction "1_1") (pintype "passive"))
      (node (ref "C49") (pin "1") (pinfunction "1_1") (pintype "passive"))
      (node (ref "D17") (pin "2") (pinfunction "C_2") (pintype "passive"))
      (node (ref "D18") (pin "2") (pinfunction "C_2") (pintype "passive"))
      (node (ref "D19") (pin "2") (pinfunction "C_2") (pintype "passive"))
      (node (ref "D20") (pin "2") (pinfunction "C_2") (pintype "passive"))
      (node (ref "D21") (pin "8") (pinfunction "VCC_8") (pintype "power_in"))
      (node (ref "D22") (pin "2") (pinfunction "C_2") (pintype "passive"))
      (node (ref "D23") (pin "2") (pinfunction "C_2") (pintype "passive"))
      (node (ref "D24") (pin "2") (pinfunction "C_2") (pintype "passive"))
      (node (ref "D25") (pin "2") (pinfunction "C_2") (pintype "passive"))
      (node (ref "D26") (pin "2") (pinfunction "C_2") (pintype "passive"))
      (node (ref "D27") (pin "2") (pinfunction "C_2") (pintype "passive"))
      (node (ref "D28") (pin "2") (pinfunction "C_2") (pintype "passive"))
      (node (ref "D29") (pin "2") (pinfunction "C_2") (pintype "passive"))
      (node (ref "D30") (pin "8") (pinfunction "VCC_8") (pintype "power_in"))
      (node (ref "D31") (pin "2") (pinfunction "C_2") (pintype "passive"))
      (node (ref "D32") (pin "2") (pinfunction "C_2") (pintype "passive"))
      (node (ref "D33") (pin "2") (pinfunction "C_2") (pintype "passive"))
      (node (ref "D34") (pin "2") (pinfunction "C_2") (pintype "passive"))
      (node (ref "R2") (pin "1") (pinfunction "1_1") (pintype "passive"))
      (node (ref "R22") (pin "1") (pinfunction "1_1") (pintype "passive"))
      (node (ref "R23") (pin "1") (pinfunction "1_1") (pintype "passive"))
      (node (ref "R24") (pin "1") (pinfunction "1_1") (pintype "passive"))
      (node (ref "TP1") (pin "TP") (pinfunction "TP_TP") (pintype "bidirectional"))
      (node (ref "U10") (pin "1") (pinfunction "VCCA_1") (pintype "power_in"))
      (node (ref "U47") (pin "D1") (pinfunction "VOUT1_D1") (pintype "power_in"))
      (node (ref "U47") (pin "E1") (pinfunction "VOUT1_E1") (pintype "power_in"))
      (node (ref "U50") (pin "24") (pinfunction "VCC_24") (pintype "bidirectional"))
      (node (ref "U51") (pin "16") (pinfunction "VCC_16") (pintype "power_in"))
      (node (ref "U51") (pin "4") (pinfunction "EN_4") (pintype "input"))
      (node (ref "U52") (pin "1") (pinfunction "VCC_1") (pintype "power_in"))
      (node (ref "U53") (pin "1") (pinfunction "VCC_1") (pintype "power_in"))
    )
    (net (code "2") (name "+5V") (class "Default")
      (node (ref "C10") (pin "2") (pinfunction "2_2") (pintype "passive"))
      (node (ref "C11") (pin "2") (pinfunction "2_2") (pintype "passive"))
      (node (ref "C12") (pin "2") (pinfunction "2_2") (pintype "passive"))
      (node (ref "C13") (pin "2") (pinfunction "2_2") (pintype "passive"))
      (node (ref "C14") (pin "2") (pinfunction "2_2") (pintype "passive"))
      (node (ref "C15") (pin "2") (pinfunction "2_2") (pintype "passive"))
      (node (ref "C16") (pin "2") (pinfunction "2_2") (pintype "passive"))
      (node (ref "C17") (pin "2") (pinfunction "2_2") (pintype "passive"))
      (node (ref "C18") (pin "2") (pinfunction "2_2") (pintype "passive"))
      (node (ref "C19") (pin "2") (pinfunction "2_2") (pintype "passive"))
      (node (ref "C2") (pin "1") (pinfunction "1_1") (pintype "passive"))
      (node (ref "C20") (pin "2") (pinfunction "2_2") (pintype "passive"))
      (node (ref "C21") (pin "2") (pinfunction "2_2") (pintype "passive"))
      (node (ref "C22") (pin "2") (pinfunction "2_2") (pintype "passive"))
      (node (ref "C23") (pin "2") (pinfunction "2_2") (pintype "passive"))
      (node (ref "C24") (pin "2") (pinfunction "2_2") (pintype "passive"))
      (node (ref "C25") (pin "2") (pinfunction "2_2") (pintype "passive"))
      (node (ref "C26") (pin "2") (pinfunction "2_2") (pintype "passive"))
      (node (ref "C27") (pin "2") (pinfunction "2_2") (pintype "passive"))
      (node (ref "C3") (pin "2") (pinfunction "2_2") (pintype "passive"))
      (node (ref "C36") (pin "2") (pinfunction "2_2") (pintype "passive"))
      (node (ref "C4") (pin "2") (pinfunction "2_2") (pintype "passive"))
      (node (ref "C42") (pin "2") (pinfunction "2_2") (pintype "passive"))
      (node (ref "C5") (pin "2") (pinfunction "2_2") (pintype "passive"))
      (node (ref "C6") (pin "2") (pinfunction "2_2") (pintype "passive"))
      (node (ref "C7") (pin "2") (pinfunction "2_2") (pintype "passive"))
      (node (ref "C8") (pin "2") (pinfunction "2_2") (pintype "passive"))
      (node (ref "C9") (pin "2") (pinfunction "2_2") (pintype "passive"))
      (node (ref "D1") (pin "C") (pinfunction "C_C") (pintype "passive"))
      (node (ref "D2") (pin "C") (pinfunction "C_C") (pintype "passive"))
      (node (ref "D3") (pin "C") (pinfunction "C_C") (pintype "passive"))
      (node (ref "D4") (pin "C") (pinfunction "C_C") (pintype "passive"))
      (node (ref "Q9") (pin "D") (pinfunction "D_D") (pintype "bidirectional"))
      (node (ref "S1") (pin "3") (pinfunction "3_3") (pintype "passive"))
      (node (ref "S2") (pin "3") (pinfunction "3_3") (pintype "passive"))
      (node (ref "S3") (pin "3") (pinfunction "3_3") (pintype "passive"))
      (node (ref "S4") (pin "3") (pinfunction "3_3") (pintype "passive"))
      (node (ref "TP2") (pin "TP") (pinfunction "TP_TP") (pintype "bidirectional"))
      (node (ref "U1") (pin "2") (pinfunction "VDD_2") (pintype "power_in"))
      (node (ref "U10") (pin "6") (pinfunction "VCCB_6") (pintype "power_in"))
      (node (ref "U11") (pin "2") (pinfunction "VDD_2") (pintype "power_in"))
      (node (ref "U12") (pin "2") (pinfunction "VDD_2") (pintype "power_in"))
      (node (ref "U13") (pin "2") (pinfunction "VDD_2") (pintype "power_in"))
      (node (ref "U14") (pin "2") (pinfunction "VDD_2") (pintype "power_in"))
      (node (ref "U15") (pin "2") (pinfunction "VDD_2") (pintype "power_in"))
      (node (ref "U16") (pin "2") (pinfunction "VDD_2") (pintype "power_in"))
      (node (ref "U17") (pin "2") (pinfunction "VDD_2") (pintype "power_in"))
      (node (ref "U18") (pin "2") (pinfunction "VDD_2") (pintype "power_in"))
      (node (ref "U19") (pin "2") (pinfunction "VDD_2") (pintype "power_in"))
      (node (ref "U2") (pin "2") (pinfunction "VDD_2") (pintype "power_in"))
      (node (ref "U20") (pin "2") (pinfunction "VDD_2") (pintype "power_in"))
      (node (ref "U21") (pin "2") (pinfunction "VDD_2") (pintype "power_in"))
      (node (ref "U22") (pin "2") (pinfunction "VDD_2") (pintype "power_in"))
      (node (ref "U23") (pin "2") (pinfunction "VDD_2") (pintype "power_in"))
      (node (ref "U24") (pin "2") (pinfunction "VDD_2") (pintype "power_in"))
      (node (ref "U25") (pin "2") (pinfunction "VDD_2") (pintype "power_in"))
      (node (ref "U26") (pin "2") (pinfunction "VDD_2") (pintype "power_in"))
      (node (ref "U27") (pin "2") (pinfunction "VDD_2") (pintype "power_in"))
      (node (ref "U28") (pin "2") (pinfunction "VDD_2") (pintype "power_in"))
      (node (ref "U29") (pin "2") (pinfunction "VDD_2") (pintype "power_in"))
      (node (ref "U3") (pin "2") (pinfunction "VDD_2") (pintype "power_in"))
      (node (ref "U30") (pin "2") (pinfunction "VDD_2") (pintype "power_in"))
      (node (ref "U31") (pin "2") (pinfunction "VDD_2") (pintype "power_in"))
      (node (ref "U32") (pin "2") (pinfunction "VDD_2") (pintype "power_in"))
      (node (ref "U33") (pin "2") (pinfunction "VDD_2") (pintype "power_in"))
      (node (ref "U34") (pin "2") (pinfunction "VDD_2") (pintype "power_in"))
      (node (ref "U35") (pin "2") (pinfunction "VDD_2") (pintype "power_in"))
      (node (ref "U36") (pin "2") (pinfunction "VDD_2") (pintype "power_in"))
      (node (ref "U37") (pin "2") (pinfunction "VDD_2") (pintype "power_in"))
      (node (ref "U38") (pin "2") (pinfunction "VDD_2") (pintype "power_in"))
      (node (ref "U39") (pin "2") (pinfunction "VDD_2") (pintype "power_in"))
      (node (ref "U4") (pin "2") (pinfunction "VDD_2") (pintype "power_in"))
      (node (ref "U40") (pin "2") (pinfunction "VDD_2") (pintype "power_in"))
      (node (ref "U41") (pin "2") (pinfunction "VDD_2") (pintype "power_in"))
      (node (ref "U42") (pin "2") (pinfunction "VDD_2") (pintype "power_in"))
      (node (ref "U43") (pin "1") (pinfunction "COIL+_1") (pintype "bidirectional"))
      (node (ref "U44") (pin "1") (pinfunction "COIL+_1") (pintype "bidirectional"))
      (node (ref "U45") (pin "1") (pinfunction "COIL+_1") (pintype "bidirectional"))
      (node (ref "U46") (pin "1") (pinfunction "COIL+_1") (pintype "bidirectional"))
      (node (ref "U47") (pin "A1") (pinfunction "VOUT2_A1") (pintype "power_in"))
      (node (ref "U47") (pin "B1") (pinfunction "VOUT2_B1") (pintype "power_in"))
      (node (ref "U48") (pin "1") (pinfunction "AVDD_1") (pintype "bidirectional"))
      (node (ref "U5") (pin "2") (pinfunction "VDD_2") (pintype "power_in"))
      (node (ref "U6") (pin "2") (pinfunction "VDD_2") (pintype "power_in"))
      (node (ref "U7") (pin "2") (pinfunction "VDD_2") (pintype "power_in"))
      (node (ref "U8") (pin "2") (pinfunction "VDD_2") (pintype "power_in"))
      (node (ref "U9") (pin "2") (pinfunction "VDD_2") (pintype "power_in"))
    )
    (net (code "3") (name "+5V0_GOOD") (class "Default")
      (node (ref "Q9") (pin "G") (pinfunction "G_G") (pintype "bidirectional"))
      (node (ref "R43") (pin "1") (pinfunction "1_1") (pintype "passive"))
      (node (ref "U47") (pin "B4") (pinfunction "PGOOD2_B4") (pintype "open_collector"))
    )
    (net (code "4") (name "+12V") (class "Default")
      (node (ref "C40") (pin "2") (pinfunction "2_2") (pintype "passive"))
      (node (ref "J32") (pin "1") (pinfunction "1_1") (pintype "bidirectional"))
      (node (ref "J32") (pin "26") (pinfunction "26_26") (pintype "bidirectional"))
      (node (ref "R43") (pin "2") (pinfunction "2_2") (pintype "passive"))
      (node (ref "TP7") (pin "1") (pinfunction "TP_1") (pintype "bidirectional"))
      (node (ref "U47") (pin "A2") (pinfunction "VIN_A2") (pintype "power_in"))
      (node (ref "U47") (pin "B2") (pinfunction "RUN2_B2") (pintype "input"))
      (node (ref "U47") (pin "B3") (pinfunction "VIN_B3") (pintype "power_in"))
      (node (ref "U47") (pin "D2") (pinfunction "RUN1_D2") (pintype "input"))
      (node (ref "U47") (pin "D3") (pinfunction "VIN_D3") (pintype "power_in"))
      (node (ref "U47") (pin "E2") (pinfunction "VIN_E2") (pintype "power_in"))
    )
    (net (code "5") (name "/3.3V") (class "Default")
      (node (ref "U49") (pin "3.3V") (pinfunction "3.3V_3.3V") (pintype "power_in"))
    )
    (net (code "6") (name "/LVDS_DIN0_N") (class "Default")
      (node (ref "J32") (pin "23") (pinfunction "23_23") (pintype "bidirectional"))
      (node (ref "U52") (pin "5") (pinfunction "BOUT-_5") (pintype "output"))
    )
    (net (code "7") (name "/LVDS_DIN0_P") (class "Default")
      (node (ref "J32") (pin "10") (pinfunction "10_10") (pintype "bidirectional"))
      (node (ref "U52") (pin "6") (pinfunction "BOUT+_6") (pintype "output"))
    )
    (net (code "8") (name "/LVDS_DIN1_N") (class "Default")
      (node (ref "J32") (pin "11") (pinfunction "11_11") (pintype "bidirectional"))
      (node (ref "U52") (pin "7") (pinfunction "AOUT-_7") (pintype "output"))
    )
    (net (code "9") (name "/LVDS_DIN1_P") (class "Default")
      (node (ref "J32") (pin "24") (pinfunction "24_24") (pintype "bidirectional"))
      (node (ref "U52") (pin "8") (pinfunction "AOUT+_8") (pintype "output"))
    )
    (net (code "10") (name "/LVDS_DIN2_N") (class "Default")
      (node (ref "J32") (pin "25") (pinfunction "25_25") (pintype "bidirectional"))
      (node (ref "U53") (pin "7") (pinfunction "AOUT-_7") (pintype "output"))
    )
    (net (code "11") (name "/LVDS_DIN2_P") (class "Default")
      (node (ref "J32") (pin "12") (pinfunction "12_12") (pintype "bidirectional"))
      (node (ref "U53") (pin "8") (pinfunction "AOUT+_8") (pintype "output"))
    )
    (net (code "12") (name "/LVDS_DOUT0_N") (class "Default")
      (node (ref "J32") (pin "8") (pinfunction "8_8") (pintype "bidirectional"))
      (node (ref "R25") (pin "1") (pinfunction "1_1") (pintype "passive"))
      (node (ref "U51") (pin "1") (pinfunction "A-_1") (pintype "input"))
    )
    (net (code "13") (name "/LVDS_DOUT0_P") (class "Default")
      (node (ref "J32") (pin "21") (pinfunction "21_21") (pintype "bidirectional"))
      (node (ref "R25") (pin "2") (pinfunction "2_2") (pintype "passive"))
      (node (ref "U51") (pin "2") (pinfunction "A+_2") (pintype "input"))
    )
    (net (code "14") (name "/LVDS_DOUT1_N") (class "Default")
      (node (ref "J32") (pin "9") (pinfunction "9_9") (pintype "bidirectional"))
      (node (ref "R26") (pin "1") (pinfunction "1_1") (pintype "passive"))
      (node (ref "U51") (pin "7") (pinfunction "B-_7") (pintype "input"))
    )
    (net (code "15") (name "/LVDS_DOUT1_P") (class "Default")
      (node (ref "J32") (pin "22") (pinfunction "22_22") (pintype "bidirectional"))
      (node (ref "R26") (pin "2") (pinfunction "2_2") (pintype "passive"))
      (node (ref "U51") (pin "6") (pinfunction "B+_6") (pintype "input"))
    )
    (net (code "16") (name "/~{TCA_INT}") (class "Default")
      (node (ref "R22") (pin "2") (pinfunction "2_2") (pintype "passive"))
      (node (ref "U50") (pin "1") (pinfunction "_INT_1") (pintype "bidirectional"))
    )
    (net (code "17") (name "AGND") (class "Default")
      (node (ref "D10") (pin "A") (pinfunction "1_A") (pintype "passive"))
      (node (ref "D11") (pin "A") (pinfunction "1_A") (pintype "passive"))
      (node (ref "D12") (pin "A") (pinfunction "1_A") (pintype "passive"))
      (node (ref "D13") (pin "A") (pinfunction "1_A") (pintype "passive"))
      (node (ref "D14") (pin "A") (pinfunction "1_A") (pintype "passive"))
      (node (ref "D15") (pin "A") (pinfunction "1_A") (pintype "passive"))
      (node (ref "D16") (pin "A") (pinfunction "1_A") (pintype "passive"))
      (node (ref "D5") (pin "A") (pinfunction "1_A") (pintype "passive"))
      (node (ref "D6") (pin "A") (pinfunction "1_A") (pintype "passive"))
      (node (ref "D7") (pin "A") (pinfunction "1_A") (pintype "passive"))
      (node (ref "D8") (pin "A") (pinfunction "1_A") (pintype "passive"))
      (node (ref "D9") (pin "A") (pinfunction "1_A") (pintype "passive"))
      (node (ref "J10") (pin "2") (pinfunction "2_2") (pintype "passive"))
      (node (ref "J10") (pin "3") (pinfunction "2_3") (pintype "passive"))
      (node (ref "J10") (pin "4") (pinfunction "2_4") (pintype "passive"))
      (node (ref "J10") (pin "5") (pinfunction "2_5") (pintype "passive"))
      (node (ref "J11") (pin "2") (pinfunction "2_2") (pintype "passive"))
      (node (ref "J11") (pin "3") (pinfunction "2_3") (pintype "passive"))
      (node (ref "J11") (pin "4") (pinfunction "2_4") (pintype "passive"))
      (node (ref "J11") (pin "5") (pinfunction "2_5") (pintype "passive"))
      (node (ref "J12") (pin "2") (pinfunction "2_2") (pintype "passive"))
      (node (ref "J12") (pin "3") (pinfunction "2_3") (pintype "passive"))
      (node (ref "J12") (pin "4") (pinfunction "2_4") (pintype "passive"))
      (node (ref "J12") (pin "5") (pinfunction "2_5") (pintype "passive"))
      (node (ref "J13") (pin "2") (pinfunction "2_2") (pintype "passive"))
      (node (ref "J13") (pin "3") (pinfunction "2_3") (pintype "passive"))
      (node (ref "J13") (pin "4") (pinfunction "2_4") (pintype "passive"))
      (node (ref "J13") (pin "5") (pinfunction "2_5") (pintype "passive"))
      (node (ref "J14") (pin "2") (pinfunction "2_2") (pintype "passive"))
      (node (ref "J14") (pin "3") (pinfunction "2_3") (pintype "passive"))
      (node (ref "J14") (pin "4") (pinfunction "2_4") (pintype "passive"))
      (node (ref "J14") (pin "5") (pinfunction "2_5") (pintype "passive"))
      (node (ref "J17") (pin "1") (pinfunction "1_1") (pintype "passive"))
      (node (ref "J17") (pin "15") (pinfunction "15_15") (pintype "passive"))
      (node (ref "J17") (pin "16") (pinfunction "16_16") (pintype "passive"))
      (node (ref "J17") (pin "17") (pinfunction "1_17") (pintype "passive"))
      (node (ref "J17") (pin "18") (pinfunction "2_18") (pintype "passive"))
      (node (ref "J17") (pin "2") (pinfunction "2_2") (pintype "passive"))
      (node (ref "J17") (pin "31") (pinfunction "15_31") (pintype "passive"))
      (node (ref "J17") (pin "32") (pinfunction "16_32") (pintype "passive"))
      (node (ref "J20") (pin "2") (pinfunction "2_2") (pintype "passive"))
      (node (ref "J20") (pin "3") (pinfunction "2_3") (pintype "passive"))
      (node (ref "J20") (pin "4") (pinfunction "2_4") (pintype "passive"))
      (node (ref "J20") (pin "5") (pinfunction "2_5") (pintype "passive"))
      (node (ref "J21") (pin "2") (pinfunction "2_2") (pintype "passive"))
      (node (ref "J21") (pin "3") (pinfunction "2_3") (pintype "passive"))
      (node (ref "J21") (pin "4") (pinfunction "2_4") (pintype "passive"))
      (node (ref "J21") (pin "5") (pinfunction "2_5") (pintype "passive"))
      (node (ref "J22") (pin "2") (pinfunction "2_2") (pintype "passive"))
      (node (ref "J22") (pin "3") (pinfunction "2_3") (pintype "passive"))
      (node (ref "J22") (pin "4") (pinfunction "2_4") (pintype "passive"))
      (node (ref "J22") (pin "5") (pinfunction "2_5") (pintype "passive"))
      (node (ref "J23") (pin "2") (pinfunction "2_2") (pintype "passive"))
      (node (ref "J23") (pin "3") (pinfunction "2_3") (pintype "passive"))
      (node (ref "J23") (pin "4") (pinfunction "2_4") (pintype "passive"))
      (node (ref "J23") (pin "5") (pinfunction "2_5") (pintype "passive"))
      (node (ref "J24") (pin "2") (pinfunction "2_2") (pintype "passive"))
      (node (ref "J24") (pin "3") (pinfunction "2_3") (pintype "passive"))
      (node (ref "J24") (pin "4") (pinfunction "2_4") (pintype "passive"))
      (node (ref "J24") (pin "5") (pinfunction "2_5") (pintype "passive"))
      (node (ref "J25") (pin "2") (pinfunction "2_2") (pintype "passive"))
      (node (ref "J25") (pin "3") (pinfunction "2_3") (pintype "passive"))
      (node (ref "J25") (pin "4") (pinfunction "2_4") (pintype "passive"))
      (node (ref "J25") (pin "5") (pinfunction "2_5") (pintype "passive"))
      (node (ref "J26") (pin "1") (pinfunction "1_1") (pintype "bidirectional"))
      (node (ref "J26") (pin "11") (pinfunction "11_11") (pintype "bidirectional"))
      (node (ref "J26") (pin "13") (pinfunction "13_13") (pintype "bidirectional"))
      (node (ref "J26") (pin "15") (pinfunction "15_15") (pintype "bidirectional"))
      (node (ref "J26") (pin "17") (pinfunction "17_17") (pintype "bidirectional"))
      (node (ref "J26") (pin "19") (pinfunction "19_19") (pintype "bidirectional"))
      (node (ref "J26") (pin "21") (pinfunction "21_21") (pintype "bidirectional"))
      (node (ref "J26") (pin "23") (pinfunction "23_23") (pintype "bidirectional"))
      (node (ref "J26") (pin "3") (pinfunction "3_3") (pintype "bidirectional"))
      (node (ref "J26") (pin "5") (pinfunction "5_5") (pintype "bidirectional"))
      (node (ref "J26") (pin "7") (pinfunction "7_7") (pintype "bidirectional"))
      (node (ref "J26") (pin "9") (pinfunction "9_9") (pintype "bidirectional"))
      (node (ref "J32") (pin "13") (pinfunction "13_13") (pintype "bidirectional"))
      (node (ref "J32") (pin "14") (pinfunction "14_14") (pintype "bidirectional"))
      (node (ref "J9") (pin "2") (pinfunction "2_2") (pintype "passive"))
      (node (ref "J9") (pin "3") (pinfunction "2_3") (pintype "passive"))
      (node (ref "J9") (pin "4") (pinfunction "2_4") (pintype "passive"))
      (node (ref "J9") (pin "5") (pinfunction "2_5") (pintype "passive"))
      (node (ref "TP6") (pin "1") (pinfunction "TP_1") (pintype "bidirectional"))
    )
    (net (code "18") (name "AIO_0") (class "Default")
      (node (ref "D5") (pin "C") (pinfunction "2_C") (pintype "passive"))
      (node (ref "J17") (pin "19") (pinfunction "3_19") (pintype "passive"))
      (node (ref "J17") (pin "3") (pinfunction "3_3") (pintype "passive"))
      (node (ref "J26") (pin "2") (pinfunction "2_2") (pintype "bidirectional"))
      (node (ref "J32") (pin "20") (pinfunction "20_20") (pintype "bidirectional"))
      (node (ref "J9") (pin "1") (pinfunction "1_1") (pintype "passive"))
    )
    (net (code "19") (name "AIO_1") (class "Default")
      (node (ref "D6") (pin "C") (pinfunction "2_C") (pintype "passive"))
      (node (ref "J10") (pin "1") (pinfunction "1_1") (pintype "passive"))
      (node (ref "J17") (pin "20") (pinfunction "4_20") (pintype "passive"))
      (node (ref "J17") (pin "4") (pinfunction "4_4") (pintype "passive"))
      (node (ref "J26") (pin "4") (pinfunction "4_4") (pintype "bidirectional"))
      (node (ref "J32") (pin "7") (pinfunction "7_7") (pintype "bidirectional"))
    )
    (net (code "20") (name "AIO_2") (class "Default")
      (node (ref "D7") (pin "C") (pinfunction "2_C") (pintype "passive"))
      (node (ref "J11") (pin "1") (pinfunction "1_1") (pintype "passive"))
      (node (ref "J17") (pin "21") (pinfunction "5_21") (pintype "passive"))
      (node (ref "J17") (pin "5") (pinfunction "5_5") (pintype "passive"))
      (node (ref "J26") (pin "6") (pinfunction "6_6") (pintype "bidirectional"))
      (node (ref "J32") (pin "19") (pinfunction "19_19") (pintype "bidirectional"))
    )
    (net (code "21") (name "AIO_3") (class "Default")
      (node (ref "D8") (pin "C") (pinfunction "2_C") (pintype "passive"))
      (node (ref "J12") (pin "1") (pinfunction "1_1") (pintype "passive"))
      (node (ref "J17") (pin "22") (pinfunction "6_22") (pintype "passive"))
      (node (ref "J17") (pin "6") (pinfunction "6_6") (pintype "passive"))
      (node (ref "J26") (pin "8") (pinfunction "8_8") (pintype "bidirectional"))
      (node (ref "J32") (pin "6") (pinfunction "6_6") (pintype "bidirectional"))
    )
    (net (code "22") (name "AIO_4") (class "Default")
      (node (ref "D9") (pin "C") (pinfunction "2_C") (pintype "passive"))
      (node (ref "J13") (pin "1") (pinfunction "1_1") (pintype "passive"))
      (node (ref "J17") (pin "23") (pinfunction "7_23") (pintype "passive"))
      (node (ref "J17") (pin "7") (pinfunction "7_7") (pintype "passive"))
      (node (ref "J26") (pin "10") (pinfunction "10_10") (pintype "bidirectional"))
      (node (ref "J32") (pin "18") (pinfunction "18_18") (pintype "bidirectional"))
    )
    (net (code "23") (name "AIO_5") (class "Default")
      (node (ref "D10") (pin "C") (pinfunction "2_C") (pintype "passive"))
      (node (ref "J14") (pin "1") (pinfunction "1_1") (pintype "passive"))
      (node (ref "J17") (pin "24") (pinfunction "8_24") (pintype "passive"))
      (node (ref "J17") (pin "8") (pinfunction "8_8") (pintype "passive"))
      (node (ref "J26") (pin "12") (pinfunction "12_12") (pintype "bidirectional"))
      (node (ref "J32") (pin "5") (pinfunction "5_5") (pintype "bidirectional"))
    )
    (net (code "24") (name "AIO_6") (class "Default")
      (node (ref "D11") (pin "C") (pinfunction "2_C") (pintype "passive"))
      (node (ref "J17") (pin "25") (pinfunction "9_25") (pintype "passive"))
      (node (ref "J17") (pin "9") (pinfunction "9_9") (pintype "passive"))
      (node (ref "J20") (pin "1") (pinfunction "1_1") (pintype "passive"))
      (node (ref "J26") (pin "14") (pinfunction "14_14") (pintype "bidirectional"))
      (node (ref "J32") (pin "17") (pinfunction "17_17") (pintype "bidirectional"))
    )
    (net (code "25") (name "AIO_7") (class "Default")
      (node (ref "D12") (pin "C") (pinfunction "2_C") (pintype "passive"))
      (node (ref "J17") (pin "10") (pinfunction "10_10") (pintype "passive"))
      (node (ref "J17") (pin "26") (pinfunction "10_26") (pintype "passive"))
      (node (ref "J21") (pin "1") (pinfunction "1_1") (pintype "passive"))
      (node (ref "J26") (pin "16") (pinfunction "16_16") (pintype "bidirectional"))
      (node (ref "J32") (pin "4") (pinfunction "4_4") (pintype "bidirectional"))
    )
    (net (code "26") (name "AIO_8") (class "Default")
      (node (ref "D13") (pin "C") (pinfunction "2_C") (pintype "passive"))
      (node (ref "J17") (pin "11") (pinfunction "11_11") (pintype "passive"))
      (node (ref "J17") (pin "27") (pinfunction "11_27") (pintype "passive"))
      (node (ref "J22") (pin "1") (pinfunction "1_1") (pintype "passive"))
      (node (ref "J26") (pin "18") (pinfunction "18_18") (pintype "bidirectional"))
      (node (ref "J32") (pin "16") (pinfunction "16_16") (pintype "bidirectional"))
    )
    (net (code "27") (name "AIO_9") (class "Default")
      (node (ref "D14") (pin "C") (pinfunction "2_C") (pintype "passive"))
      (node (ref "J17") (pin "12") (pinfunction "12_12") (pintype "passive"))
      (node (ref "J17") (pin "28") (pinfunction "12_28") (pintype "passive"))
      (node (ref "J23") (pin "1") (pinfunction "1_1") (pintype "passive"))
      (node (ref "J26") (pin "20") (pinfunction "20_20") (pintype "bidirectional"))
      (node (ref "J32") (pin "3") (pinfunction "3_3") (pintype "bidirectional"))
    )
    (net (code "28") (name "AIO_10") (class "Default")
      (node (ref "D15") (pin "C") (pinfunction "2_C") (pintype "passive"))
      (node (ref "J17") (pin "13") (pinfunction "13_13") (pintype "passive"))
      (node (ref "J17") (pin "29") (pinfunction "13_29") (pintype "passive"))
      (node (ref "J24") (pin "1") (pinfunction "1_1") (pintype "passive"))
      (node (ref "J26") (pin "22") (pinfunction "22_22") (pintype "bidirectional"))
      (node (ref "J32") (pin "15") (pinfunction "15_15") (pintype "bidirectional"))
    )
    (net (code "29") (name "AIO_11") (class "Default")
      (node (ref "D16") (pin "C") (pinfunction "2_C") (pintype "passive"))
      (node (ref "J17") (pin "14") (pinfunction "14_14") (pintype "passive"))
      (node (ref "J17") (pin "30") (pinfunction "14_30") (pintype "passive"))
      (node (ref "J25") (pin "1") (pinfunction "1_1") (pintype "passive"))
      (node (ref "J26") (pin "24") (pinfunction "24_24") (pintype "bidirectional"))
      (node (ref "J32") (pin "2") (pinfunction "2_2") (pintype "bidirectional"))
    )
    (net (code "30") (name "BUTTON0") (class "Default")
      (node (ref "S5") (pin "SW1") (pinfunction "P_SW1") (pintype "passive"))
      (node (ref "U50") (pin "16") (pinfunction "P13_16") (pintype "bidirectional"))
    )
    (net (code "31") (name "BUTTON1") (class "Default")
      (node (ref "S7") (pin "SW1") (pinfunction "P_SW1") (pintype "passive"))
      (node (ref "U50") (pin "17") (pinfunction "P14_17") (pintype "bidirectional"))
    )
    (net (code "32") (name "BUTTON2") (class "Default")
      (node (ref "S9") (pin "SW1") (pinfunction "P_SW1") (pintype "passive"))
      (node (ref "U50") (pin "18") (pinfunction "P15_18") (pintype "bidirectional"))
    )
    (net (code "33") (name "BUTTON3") (class "Default")
      (node (ref "S6") (pin "SW1") (pinfunction "P_SW1") (pintype "passive"))
      (node (ref "U50") (pin "11") (pinfunction "P07_11") (pintype "bidirectional"))
    )
    (net (code "34") (name "BUTTON4") (class "Default")
      (node (ref "S8") (pin "SW1") (pinfunction "P_SW1") (pintype "passive"))
      (node (ref "U50") (pin "14") (pinfunction "P11_14") (pintype "bidirectional"))
    )
    (net (code "35") (name "BUTTON5") (class "Default")
      (node (ref "S10") (pin "SW1") (pinfunction "P_SW1") (pintype "passive"))
      (node (ref "U50") (pin "10") (pinfunction "P06_10") (pintype "bidirectional"))
    )
    (net (code "36") (name "DIN0") (class "Default")
      (node (ref "D30") (pin "4") (pinfunction "CH4_4") (pintype "passive"))
      (node (ref "J34") (pin "2") (pinfunction "2_2") (pintype "passive"))
      (node (ref "J35") (pin "11") (pinfunction "2_11") (pintype "passive"))
      (node (ref "J35") (pin "2") (pinfunction "2_2") (pintype "passive"))
      (node (ref "R42") (pin "2") (pinfunction "2_2") (pintype "passive"))
    )
    (net (code "37") (name "DIN0_P") (class "Default")
      (node (ref "D34") (pin "3") (pinfunction "COMM_3") (pintype "passive"))
      (node (ref "R42") (pin "1") (pinfunction "1_1") (pintype "passive"))
      (node (ref "U49") (pin "14") (pinfunction "14_14") (pintype "bidirectional"))
    )
    (net (code "38") (name "DIN1") (class "Default")
      (node (ref "D30") (pin "3") (pinfunction "CH3_3") (pintype "passive"))
      (node (ref "J34") (pin "4") (pinfunction "4_4") (pintype "passive"))
      (node (ref "J35") (pin "12") (pinfunction "3_12") (pintype "passive"))
      (node (ref "J35") (pin "3") (pinfunction "3_3") (pintype "passive"))
      (node (ref "R34") (pin "2") (pinfunction "2_2") (pintype "passive"))
    )
    (net (code "39") (name "DIN1_P") (class "Default")
      (node (ref "D25") (pin "3") (pinfunction "COMM_3") (pintype "passive"))
      (node (ref "R34") (pin "1") (pinfunction "1_1") (pintype "passive"))
      (node (ref "U49") (pin "15") (pinfunction "15_15") (pintype "bidirectional"))
    )
    (net (code "40") (name "DIN2") (class "Default")
      (node (ref "D30") (pin "2") (pinfunction "CH2_2") (pintype "passive"))
      (node (ref "J34") (pin "6") (pinfunction "6_6") (pintype "passive"))
      (node (ref "J35") (pin "13") (pinfunction "4_13") (pintype "passive"))
      (node (ref "J35") (pin "4") (pinfunction "4_4") (pintype "passive"))
      (node (ref "R40") (pin "2") (pinfunction "2_2") (pintype "passive"))
    )
    (net (code "41") (name "DIN2_P") (class "Default")
      (node (ref "D32") (pin "3") (pinfunction "COMM_3") (pintype "passive"))
      (node (ref "R40") (pin "1") (pinfunction "1_1") (pintype "passive"))
      (node (ref "U49") (pin "16") (pinfunction "16/GBIN2_16") (pintype "bidirectional"))
    )
    (net (code "42") (name "DIN3") (class "Default")
      (node (ref "D30") (pin "1") (pinfunction "CH1_1") (pintype "passive"))
      (node (ref "J34") (pin "8") (pinfunction "8_8") (pintype "passive"))
      (node (ref "J35") (pin "14") (pinfunction "5_14") (pintype "passive"))
      (node (ref "J35") (pin "5") (pinfunction "5_5") (pintype "passive"))
      (node (ref "R32") (pin "2") (pinfunction "2_2") (pintype "passive"))
    )
    (net (code "43") (name "DIN3_P") (class "Default")
      (node (ref "D23") (pin "3") (pinfunction "COMM_3") (pintype "passive"))
      (node (ref "R32") (pin "1") (pinfunction "1_1") (pintype "passive"))
      (node (ref "U49") (pin "9") (pinfunction "9/10B_9") (pintype "bidirectional"))
    )
    (net (code "44") (name "DIN4") (class "Default")
      (node (ref "D30") (pin "10") (pinfunction "CH8_10") (pintype "passive"))
      (node (ref "J34") (pin "10") (pinfunction "10_10") (pintype "passive"))
      (node (ref "J35") (pin "15") (pinfunction "6_15") (pintype "passive"))
      (node (ref "J35") (pin "6") (pinfunction "6_6") (pintype "passive"))
      (node (ref "R38") (pin "2") (pinfunction "2_2") (pintype "passive"))
    )
    (net (code "45") (name "DIN4_P") (class "Default")
      (node (ref "D29") (pin "3") (pinfunction "COMM_3") (pintype "passive"))
      (node (ref "R38") (pin "1") (pinfunction "1_1") (pintype "passive"))
      (node (ref "U49") (pin "10") (pinfunction "10/26A_10") (pintype "bidirectional"))
    )
    (net (code "46") (name "DIN5") (class "Default")
      (node (ref "D30") (pin "9") (pinfunction "CH7_9") (pintype "passive"))
      (node (ref "J34") (pin "12") (pinfunction "12_12") (pintype "passive"))
      (node (ref "J35") (pin "16") (pinfunction "7_16") (pintype "passive"))
      (node (ref "J35") (pin "7") (pinfunction "7_7") (pintype "passive"))
      (node (ref "R30") (pin "2") (pinfunction "2_2") (pintype "passive"))
    )
    (net (code "47") (name "DIN5_P") (class "Default")
      (node (ref "D20") (pin "3") (pinfunction "COMM_3") (pintype "passive"))
      (node (ref "R30") (pin "1") (pinfunction "1_1") (pintype "passive"))
      (node (ref "U49") (pin "11") (pinfunction "11_11") (pintype "bidirectional"))
    )
    (net (code "48") (name "DIN6") (class "Default")
      (node (ref "D30") (pin "7") (pinfunction "CH6_7") (pintype "passive"))
      (node (ref "J34") (pin "14") (pinfunction "14_14") (pintype "passive"))
      (node (ref "J35") (pin "17") (pinfunction "8_17") (pintype "passive"))
      (node (ref "J35") (pin "8") (pinfunction "8_8") (pintype "passive"))
      (node (ref "R36") (pin "2") (pinfunction "2_2") (pintype "passive"))
    )
    (net (code "49") (name "DIN6_P") (class "Default")
      (node (ref "D27") (pin "3") (pinfunction "COMM_3") (pintype "passive"))
      (node (ref "R36") (pin "1") (pinfunction "1_1") (pintype "passive"))
      (node (ref "U49") (pin "12") (pinfunction "12_12") (pintype "bidirectional"))
    )
    (net (code "50") (name "DIN7") (class "Default")
      (node (ref "D30") (pin "6") (pinfunction "CH5_6") (pintype "passive"))
      (node (ref "J34") (pin "16") (pinfunction "16_16") (pintype "passive"))
      (node (ref "J35") (pin "18") (pinfunction "9_18") (pintype "passive"))
      (node (ref "J35") (pin "9") (pinfunction "9_9") (pintype "passive"))
      (node (ref "R28") (pin "2") (pinfunction "2_2") (pintype "passive"))
    )
    (net (code "51") (name "DIN7_P") (class "Default")
      (node (ref "D18") (pin "3") (pinfunction "COMM_3") (pintype "passive"))
      (node (ref "R28") (pin "1") (pinfunction "1_1") (pintype "passive"))
      (node (ref "U49") (pin "13") (pinfunction "13/26B_13") (pintype "bidirectional"))
    )
    (net (code "52") (name "DOUT0") (class "Default")
      (node (ref "D21") (pin "10") (pinfunction "CH8_10") (pintype "passive"))
      (node (ref "J31") (pin "2") (pinfunction "2_2") (pintype "passive"))
      (node (ref "J33") (pin "11") (pinfunction "2_11") (pintype "passive"))
      (node (ref "J33") (pin "2") (pinfunction "2_2") (pintype "passive"))
      (node (ref "R27") (pin "2") (pinfunction "2_2") (pintype "passive"))
    )
    (net (code "53") (name "DOUT0_P") (class "Default")
      (node (ref "D17") (pin "3") (pinfunction "COMM_3") (pintype "passive"))
      (node (ref "R27") (pin "1") (pinfunction "1_1") (pintype "passive"))
      (node (ref "U49") (pin "8") (pinfunction "8_8") (pintype "bidirectional"))
    )
    (net (code "54") (name "DOUT1") (class "Default")
      (node (ref "D21") (pin "9") (pinfunction "CH7_9") (pintype "passive"))
      (node (ref "J31") (pin "4") (pinfunction "4_4") (pintype "passive"))
      (node (ref "J33") (pin "12") (pinfunction "3_12") (pintype "passive"))
      (node (ref "J33") (pin "3") (pinfunction "3_3") (pintype "passive"))
      (node (ref "R29") (pin "2") (pinfunction "2_2") (pintype "passive"))
    )
    (net (code "55") (name "DOUT1_P") (class "Default")
      (node (ref "D19") (pin "3") (pinfunction "COMM_3") (pintype "passive"))
      (node (ref "R29") (pin "1") (pinfunction "1_1") (pintype "passive"))
      (node (ref "U49") (pin "7") (pinfunction "7/10A_7") (pintype "bidirectional"))
    )
    (net (code "56") (name "DOUT2") (class "Default")
      (node (ref "D21") (pin "7") (pinfunction "CH6_7") (pintype "passive"))
      (node (ref "J31") (pin "6") (pinfunction "6_6") (pintype "passive"))
      (node (ref "J33") (pin "13") (pinfunction "4_13") (pintype "passive"))
      (node (ref "J33") (pin "4") (pinfunction "4_4") (pintype "passive"))
      (node (ref "R31") (pin "2") (pinfunction "2_2") (pintype "passive"))
    )
    (net (code "57") (name "DOUT2_P") (class "Default")
      (node (ref "D22") (pin "3") (pinfunction "COMM_3") (pintype "passive"))
      (node (ref "R31") (pin "1") (pinfunction "1_1") (pintype "passive"))
      (node (ref "U49") (pin "6") (pinfunction "6_6") (pintype "bidirectional"))
    )
    (net (code "58") (name "DOUT3") (class "Default")
      (node (ref "D21") (pin "6") (pinfunction "CH5_6") (pintype "passive"))
      (node (ref "J31") (pin "8") (pinfunction "8_8") (pintype "passive"))
      (node (ref "J33") (pin "14") (pinfunction "5_14") (pintype "passive"))
      (node (ref "J33") (pin "5") (pinfunction "5_5") (pintype "passive"))
      (node (ref "R33") (pin "2") (pinfunction "2_2") (pintype "passive"))
    )
    (net (code "59") (name "DOUT3_P") (class "Default")
      (node (ref "D24") (pin "3") (pinfunction "COMM_3") (pintype "passive"))
      (node (ref "R33") (pin "1") (pinfunction "1_1") (pintype "passive"))
      (node (ref "U49") (pin "5") (pinfunction "5/3B_5") (pintype "bidirectional"))
    )
    (net (code "60") (name "DOUT4") (class "Default")
      (node (ref "D21") (pin "1") (pinfunction "CH1_1") (pintype "passive"))
      (node (ref "J31") (pin "10") (pinfunction "10_10") (pintype "passive"))
      (node (ref "J33") (pin "15") (pinfunction "6_15") (pintype "passive"))
      (node (ref "J33") (pin "6") (pinfunction "6_6") (pintype "passive"))
      (node (ref "R35") (pin "2") (pinfunction "2_2") (pintype "passive"))
    )
    (net (code "61") (name "DOUT4_P") (class "Default")
      (node (ref "D26") (pin "3") (pinfunction "COMM_3") (pintype "passive"))
      (node (ref "R35") (pin "1") (pinfunction "1_1") (pintype "passive"))
      (node (ref "U49") (pin "4") (pinfunction "4_4") (pintype "bidirectional"))
    )
    (net (code "62") (name "DOUT5") (class "Default")
      (node (ref "D21") (pin "2") (pinfunction "CH2_2") (pintype "passive"))
      (node (ref "J31") (pin "12") (pinfunction "12_12") (pintype "passive"))
      (node (ref "J33") (pin "16") (pinfunction "7_16") (pintype "passive"))
      (node (ref "J33") (pin "7") (pinfunction "7_7") (pintype "passive"))
      (node (ref "R37") (pin "2") (pinfunction "2_2") (pintype "passive"))
    )
    (net (code "63") (name "DOUT5_P") (class "Default")
      (node (ref "D28") (pin "3") (pinfunction "COMM_3") (pintype "passive"))
      (node (ref "R37") (pin "1") (pinfunction "1_1") (pintype "passive"))
      (node (ref "U49") (pin "3") (pinfunction "3/3A_3") (pintype "bidirectional"))
    )
    (net (code "64") (name "DOUT6") (class "Default")
      (node (ref "D21") (pin "3") (pinfunction "CH3_3") (pintype "passive"))
      (node (ref "J31") (pin "14") (pinfunction "14_14") (pintype "passive"))
      (node (ref "J33") (pin "17") (pinfunction "8_17") (pintype "passive"))
      (node (ref "J33") (pin "8") (pinfunction "8_8") (pintype "passive"))
      (node (ref "R39") (pin "2") (pinfunction "2_2") (pintype "passive"))
    )
    (net (code "65") (name "DOUT6_P") (class "Default")
      (node (ref "D31") (pin "3") (pinfunction "COMM_3") (pintype "passive"))
      (node (ref "R39") (pin "1") (pinfunction "1_1") (pintype "passive"))
      (node (ref "U49") (pin "2") (pinfunction "2_2") (pintype "bidirectional"))
    )
    (net (code "66") (name "DOUT7") (class "Default")
      (node (ref "D21") (pin "4") (pinfunction "CH4_4") (pintype "passive"))
      (node (ref "J31") (pin "16") (pinfunction "16_16") (pintype "passive"))
      (node (ref "J33") (pin "18") (pinfunction "9_18") (pintype "passive"))
      (node (ref "J33") (pin "9") (pinfunction "9_9") (pintype "passive"))
      (node (ref "R41") (pin "2") (pinfunction "2_2") (pintype "passive"))
    )
    (net (code "67") (name "DOUT7_P") (class "Default")
      (node (ref "D33") (pin "3") (pinfunction "COMM_3") (pintype "passive"))
      (node (ref "R41") (pin "1") (pinfunction "1_1") (pintype "passive"))
      (node (ref "U49") (pin "1") (pinfunction "1_1") (pintype "bidirectional"))
    )
    (net (code "68") (name "GND") (class "Default")
      (node (ref "C1") (pin "2") (pinfunction "2_2") (pintype "passive"))
      (node (ref "C10") (pin "1") (pinfunction "1_1") (pintype "passive"))
      (node (ref "C11") (pin "1") (pinfunction "1_1") (pintype "passive"))
      (node (ref "C12") (pin "1") (pinfunction "1_1") (pintype "passive"))
      (node (ref "C13") (pin "1") (pinfunction "1_1") (pintype "passive"))
      (node (ref "C14") (pin "1") (pinfunction "1_1") (pintype "passive"))
      (node (ref "C15") (pin "1") (pinfunction "1_1") (pintype "passive"))
      (node (ref "C16") (pin "1") (pinfunction "1_1") (pintype "passive"))
      (node (ref "C17") (pin "1") (pinfunction "1_1") (pintype "passive"))
      (node (ref "C18") (pin "1") (pinfunction "1_1") (pintype "passive"))
      (node (ref "C19") (pin "1") (pinfunction "1_1") (pintype "passive"))
      (node (ref "C2") (pin "2") (pinfunction "2_2") (pintype "passive"))
      (node (ref "C20") (pin "1") (pinfunction "1_1") (pintype "passive"))
      (node (ref "C21") (pin "1") (pinfunction "1_1") (pintype "passive"))
      (node (ref "C22") (pin "1") (pinfunction "1_1") (pintype "passive"))
      (node (ref "C23") (pin "1") (pinfunction "1_1") (pintype "passive"))
      (node (ref "C24") (pin "1") (pinfunction "1_1") (pintype "passive"))
      (node (ref "C25") (pin "1") (pinfunction "1_1") (pintype "passive"))
      (node (ref "C26") (pin "1") (pinfunction "1_1") (pintype "passive"))
      (node (ref "C27") (pin "1") (pinfunction "1_1") (pintype "passive"))
      (node (ref "C28") (pin "1") (pinfunction "1_1") (pintype "passive"))
      (node (ref "C29") (pin "1") (pinfunction "1_1") (pintype "passive"))
      (node (ref "C3") (pin "1") (pinfunction "1_1") (pintype "passive"))
      (node (ref "C30") (pin "1") (pinfunction "1_1") (pintype "passive"))
      (node (ref "C31") (pin "1") (pinfunction "1_1") (pintype "passive"))
      (node (ref "C36") (pin "1") (pinfunction "1_1") (pintype "passive"))
      (node (ref "C37") (pin "1") (pinfunction "1_1") (pintype "passive"))
      (node (ref "C38") (pin "1") (pinfunction "1_1") (pintype "passive"))
      (node (ref "C39") (pin "1") (pinfunction "1_1") (pintype "passive"))
      (node (ref "C4") (pin "1") (pinfunction "1_1") (pintype "passive"))
      (node (ref "C40") (pin "1") (pinfunction "1_1") (pintype "passive"))
      (node (ref "C42") (pin "1") (pinfunction "1_1") (pintype "passive"))
      (node (ref "C43") (pin "1") (pinfunction "1_1") (pintype "passive"))
      (node (ref "C44") (pin "2") (pinfunction "2_2") (pintype "passive"))
      (node (ref "C45") (pin "2") (pinfunction "2_2") (pintype "passive"))
      (node (ref "C46") (pin "2") (pinfunction "2_2") (pintype "passive"))
      (node (ref "C47") (pin "2") (pinfunction "2_2") (pintype "passive"))
      (node (ref "C48") (pin "2") (pinfunction "2_2") (pintype "passive"))
      (node (ref "C49") (pin "2") (pinfunction "2_2") (pintype "passive"))
      (node (ref "C5") (pin "1") (pinfunction "1_1") (pintype "passive"))
      (node (ref "C6") (pin "1") (pinfunction "1_1") (pintype "passive"))
      (node (ref "C7") (pin "1") (pinfunction "1_1") (pintype "passive"))
      (node (ref "C8") (pin "1") (pinfunction "1_1") (pintype "passive"))
      (node (ref "C9") (pin "1") (pinfunction "1_1") (pintype "passive"))
      (node (ref "D17") (pin "1") (pinfunction "A_1") (pintype "passive"))
      (node (ref "D18") (pin "1") (pinfunction "A_1") (pintype "passive"))
      (node (ref "D19") (pin "1") (pinfunction "A_1") (pintype "passive"))
      (node (ref "D20") (pin "1") (pinfunction "A_1") (pintype "passive"))
      (node (ref "D21") (pin "5") (pinfunction "VSS_5") (pintype "power_in"))
      (node (ref "D22") (pin "1") (pinfunction "A_1") (pintype "passive"))
      (node (ref "D23") (pin "1") (pinfunction "A_1") (pintype "passive"))
      (node (ref "D24") (pin "1") (pinfunction "A_1") (pintype "passive"))
      (node (ref "D25") (pin "1") (pinfunction "A_1") (pintype "passive"))
      (node (ref "D26") (pin "1") (pinfunction "A_1") (pintype "passive"))
      (node (ref "D27") (pin "1") (pinfunction "A_1") (pintype "passive"))
      (node (ref "D28") (pin "1") (pinfunction "A_1") (pintype "passive"))
      (node (ref "D29") (pin "1") (pinfunction "A_1") (pintype "passive"))
      (node (ref "D30") (pin "5") (pinfunction "VSS_5") (pintype "power_in"))
      (node (ref "D31") (pin "1") (pinfunction "A_1") (pintype "passive"))
      (node (ref "D32") (pin "1") (pinfunction "A_1") (pintype "passive"))
      (node (ref "D33") (pin "1") (pinfunction "A_1") (pintype "passive"))
      (node (ref "D34") (pin "1") (pinfunction "A_1") (pintype "passive"))
      (node (ref "J1") (pin "GND$1") (pinfunction "2_GND$1") (pintype "passive"))
      (node (ref "J1") (pin "GND$2") (pinfunction "2_GND$2") (pintype "passive"))
      (node (ref "J1") (pin "GND$3") (pinfunction "2_GND$3") (pintype "passive"))
      (node (ref "J1") (pin "GND$4") (pinfunction "2_GND$4") (pintype "passive"))
      (node (ref "J15") (pin "GND@1") (pinfunction "2_GND@1") (pintype "passive"))
      (node (ref "J15") (pin "GND@2") (pinfunction "2_GND@2") (pintype "passive"))
      (node (ref "J15") (pin "GND@3") (pinfunction "2_GND@3") (pintype "passive"))
      (node (ref "J15") (pin "GND@4") (pinfunction "2_GND@4") (pintype "passive"))
      (node (ref "J16") (pin "GND$1") (pinfunction "2_GND$1") (pintype "passive"))
      (node (ref "J16") (pin "GND$2") (pinfunction "2_GND$2") (pintype "passive"))
      (node (ref "J16") (pin "GND$3") (pinfunction "2_GND$3") (pintype "passive"))
      (node (ref "J16") (pin "GND$4") (pinfunction "2_GND$4") (pintype "passive"))
      (node (ref "J18") (pin "GND@1") (pinfunction "2_GND@1") (pintype "passive"))
      (node (ref "J18") (pin "GND@2") (pinfunction "2_GND@2") (pintype "passive"))
      (node (ref "J18") (pin "GND@3") (pinfunction "2_GND@3") (pintype "passive"))
      (node (ref "J18") (pin "GND@4") (pinfunction "2_GND@4") (pintype "passive"))
      (node (ref "J19") (pin "GND$1") (pinfunction "2_GND$1") (pintype "passive"))
      (node (ref "J19") (pin "GND$2") (pinfunction "2_GND$2") (pintype "passive"))
      (node (ref "J19") (pin "GND$3") (pinfunction "2_GND$3") (pintype "passive"))
      (node (ref "J19") (pin "GND$4") (pinfunction "2_GND$4") (pintype "passive"))
      (node (ref "J2") (pin "GND$1") (pinfunction "2_GND$1") (pintype "passive"))
      (node (ref "J2") (pin "GND$2") (pinfunction "2_GND$2") (pintype "passive"))
      (node (ref "J2") (pin "GND$3") (pinfunction "2_GND$3") (pintype "passive"))
      (node (ref "J2") (pin "GND$4") (pinfunction "2_GND$4") (pintype "passive"))
      (node (ref "J27") (pin "GND@1") (pinfunction "2_GND@1") (pintype "passive"))
      (node (ref "J27") (pin "GND@2") (pinfunction "2_GND@2") (pintype "passive"))
      (node (ref "J27") (pin "GND@3") (pinfunction "2_GND@3") (pintype "passive"))
      (node (ref "J27") (pin "GND@4") (pinfunction "2_GND@4") (pintype "passive"))
      (node (ref "J28") (pin "GND$1") (pinfunction "2_GND$1") (pintype "passive"))
      (node (ref "J28") (pin "GND$2") (pinfunction "2_GND$2") (pintype "passive"))
      (node (ref "J28") (pin "GND$3") (pinfunction "2_GND$3") (pintype "passive"))
      (node (ref "J28") (pin "GND$4") (pinfunction "2_GND$4") (pintype "passive"))
      (node (ref "J3") (pin "GND$1") (pinfunction "2_GND$1") (pintype "passive"))
      (node (ref "J3") (pin "GND$2") (pinfunction "2_GND$2") (pintype "passive"))
      (node (ref "J3") (pin "GND$3") (pinfunction "2_GND$3") (pintype "passive"))
      (node (ref "J3") (pin "GND$4") (pinfunction "2_GND$4") (pintype "passive"))
      (node (ref "J30") (pin "2") (pinfunction "2_2") (pintype "passive"))
      (node (ref "J31") (pin "1") (pinfunction "1_1") (pintype "passive"))
      (node (ref "J31") (pin "11") (pinfunction "11_11") (pintype "passive"))
      (node (ref "J31") (pin "13") (pinfunction "13_13") (pintype "passive"))
      (node (ref "J31") (pin "15") (pinfunction "15_15") (pintype "passive"))
      (node (ref "J31") (pin "3") (pinfunction "3_3") (pintype "passive"))
      (node (ref "J31") (pin "5") (pinfunction "5_5") (pintype "passive"))
      (node (ref "J31") (pin "7") (pinfunction "7_7") (pintype "passive"))
      (node (ref "J31") (pin "9") (pinfunction "9_9") (pintype "passive"))
      (node (ref "J32") (pin "PAD1") (pinfunction "PAD1_PAD1") (pintype "bidirectional"))
      (node (ref "J32") (pin "PAD2") (pinfunction "PAD2_PAD2") (pintype "bidirectional"))
      (node (ref "J33") (pin "1") (pinfunction "1_1") (pintype "passive"))
      (node (ref "J33") (pin "10") (pinfunction "1_10") (pintype "passive"))
      (node (ref "J34") (pin "1") (pinfunction "1_1") (pintype "passive"))
      (node (ref "J34") (pin "11") (pinfunction "11_11") (pintype "passive"))
      (node (ref "J34") (pin "13") (pinfunction "13_13") (pintype "passive"))
      (node (ref "J34") (pin "15") (pinfunction "15_15") (pintype "passive"))
      (node (ref "J34") (pin "3") (pinfunction "3_3") (pintype "passive"))
      (node (ref "J34") (pin "5") (pinfunction "5_5") (pintype "passive"))
      (node (ref "J34") (pin "7") (pinfunction "7_7") (pintype "passive"))
      (node (ref "J34") (pin "9") (pinfunction "9_9") (pintype "passive"))
      (node (ref "J35") (pin "1") (pinfunction "1_1") (pintype "passive"))
      (node (ref "J35") (pin "10") (pinfunction "1_10") (pintype "passive"))
      (node (ref "J4") (pin "GND$1") (pinfunction "2_GND$1") (pintype "passive"))
      (node (ref "J4") (pin "GND$2") (pinfunction "2_GND$2") (pintype "passive"))
      (node (ref "J4") (pin "GND$3") (pinfunction "2_GND$3") (pintype "passive"))
      (node (ref "J4") (pin "GND$4") (pinfunction "2_GND$4") (pintype "passive"))
      (node (ref "J5") (pin "GND@1") (pinfunction "2_GND@1") (pintype "passive"))
      (node (ref "J5") (pin "GND@2") (pinfunction "2_GND@2") (pintype "passive"))
      (node (ref "J5") (pin "GND@3") (pinfunction "2_GND@3") (pintype "passive"))
      (node (ref "J5") (pin "GND@4") (pinfunction "2_GND@4") (pintype "passive"))
      (node (ref "J6") (pin "GND@1") (pinfunction "2_GND@1") (pintype "passive"))
      (node (ref "J6") (pin "GND@2") (pinfunction "2_GND@2") (pintype "passive"))
      (node (ref "J6") (pin "GND@3") (pinfunction "2_GND@3") (pintype "passive"))
      (node (ref "J6") (pin "GND@4") (pinfunction "2_GND@4") (pintype "passive"))
      (node (ref "J7") (pin "GND@1") (pinfunction "2_GND@1") (pintype "passive"))
      (node (ref "J7") (pin "GND@2") (pinfunction "2_GND@2") (pintype "passive"))
      (node (ref "J7") (pin "GND@3") (pinfunction "2_GND@3") (pintype "passive"))
      (node (ref "J7") (pin "GND@4") (pinfunction "2_GND@4") (pintype "passive"))
      (node (ref "J8") (pin "GND@1") (pinfunction "2_GND@1") (pintype "passive"))
      (node (ref "J8") (pin "GND@2") (pinfunction "2_GND@2") (pintype "passive"))
      (node (ref "J8") (pin "GND@3") (pinfunction "2_GND@3") (pintype "passive"))
      (node (ref "J8") (pin "GND@4") (pinfunction "2_GND@4") (pintype "passive"))
      (node (ref "Q5") (pin "2") (pinfunction "S_2") (pintype "bidirectional"))
      (node (ref "Q6") (pin "2") (pinfunction "S_2") (pintype "bidirectional"))
      (node (ref "Q7") (pin "2") (pinfunction "S_2") (pintype "bidirectional"))
      (node (ref "Q8") (pin "2") (pinfunction "S_2") (pintype "bidirectional"))
      (node (ref "R10") (pin "2") (pinfunction "2_2") (pintype "passive"))
      (node (ref "R11") (pin "1") (pinfunction "1_1") (pintype "passive"))
      (node (ref "R12") (pin "1") (pinfunction "1_1") (pintype "passive"))
      (node (ref "R13") (pin "1") (pinfunction "1_1") (pintype "passive"))
      (node (ref "R14") (pin "1") (pinfunction "1_1") (pintype "passive"))
      (node (ref "R15") (pin "1") (pinfunction "1_1") (pintype "passive"))
      (node (ref "R16") (pin "1") (pinfunction "1_1") (pintype "passive"))
      (node (ref "R17") (pin "1") (pinfunction "1_1") (pintype "passive"))
      (node (ref "R18") (pin "1") (pinfunction "1_1") (pintype "passive"))
      (node (ref "R19") (pin "2") (pinfunction "2_2") (pintype "passive"))
      (node (ref "R20") (pin "2") (pinfunction "2_2") (pintype "passive"))
      (node (ref "R21") (pin "2") (pinfunction "2_2") (pintype "passive"))
      (node (ref "R7") (pin "2") (pinfunction "2_2") (pintype "passive"))
      (node (ref "R8") (pin "2") (pinfunction "2_2") (pintype "passive"))
      (node (ref "R9") (pin "2") (pinfunction "2_2") (pintype "passive"))
      (node (ref "S1") (pin "2") (pinfunction "1_2") (pintype "passive"))
      (node (ref "S10") (pin "SW2") (pinfunction "S_SW2") (pintype "passive"))
      (node (ref "S2") (pin "2") (pinfunction "1_2") (pintype "passive"))
      (node (ref "S3") (pin "2") (pinfunction "1_2") (pintype "passive"))
      (node (ref "S4") (pin "2") (pinfunction "1_2") (pintype "passive"))
      (node (ref "S5") (pin "SW2") (pinfunction "S_SW2") (pintype "passive"))
      (node (ref "S6") (pin "SW2") (pinfunction "S_SW2") (pintype "passive"))
      (node (ref "S7") (pin "SW2") (pinfunction "S_SW2") (pintype "passive"))
      (node (ref "S8") (pin "SW2") (pinfunction "S_SW2") (pintype "passive"))
      (node (ref "S9") (pin "SW2") (pinfunction "S_SW2") (pintype "passive"))
      (node (ref "TP3") (pin "1") (pinfunction "TP_1") (pintype "bidirectional"))
      (node (ref "TP4") (pin "1") (pinfunction "TP_1") (pintype "bidirectional"))
      (node (ref "TP5") (pin "1") (pinfunction "TP_1") (pintype "bidirectional"))
      (node (ref "U1") (pin "4") (pinfunction "GND_4") (pintype "power_in"))
      (node (ref "U10") (pin "2") (pinfunction "GND_2") (pintype "power_in"))
      (node (ref "U11") (pin "4") (pinfunction "GND_4") (pintype "power_in"))
      (node (ref "U12") (pin "4") (pinfunction "GND_4") (pintype "power_in"))
      (node (ref "U13") (pin "4") (pinfunction "GND_4") (pintype "power_in"))
      (node (ref "U14") (pin "4") (pinfunction "GND_4") (pintype "power_in"))
      (node (ref "U15") (pin "4") (pinfunction "GND_4") (pintype "power_in"))
      (node (ref "U16") (pin "4") (pinfunction "GND_4") (pintype "power_in"))
      (node (ref "U17") (pin "4") (pinfunction "GND_4") (pintype "power_in"))
      (node (ref "U18") (pin "4") (pinfunction "GND_4") (pintype "power_in"))
      (node (ref "U19") (pin "4") (pinfunction "GND_4") (pintype "power_in"))
      (node (ref "U2") (pin "4") (pinfunction "GND_4") (pintype "power_in"))
      (node (ref "U20") (pin "4") (pinfunction "GND_4") (pintype "power_in"))
      (node (ref "U21") (pin "4") (pinfunction "GND_4") (pintype "power_in"))
      (node (ref "U22") (pin "4") (pinfunction "GND_4") (pintype "power_in"))
      (node (ref "U23") (pin "4") (pinfunction "GND_4") (pintype "power_in"))
      (node (ref "U24") (pin "4") (pinfunction "GND_4") (pintype "power_in"))
      (node (ref "U25") (pin "4") (pinfunction "GND_4") (pintype "power_in"))
      (node (ref "U26") (pin "4") (pinfunction "GND_4") (pintype "power_in"))
      (node (ref "U27") (pin "4") (pinfunction "GND_4") (pintype "power_in"))
      (node (ref "U28") (pin "4") (pinfunction "GND_4") (pintype "power_in"))
      (node (ref "U29") (pin "4") (pinfunction "GND_4") (pintype "power_in"))
      (node (ref "U3") (pin "4") (pinfunction "GND_4") (pintype "power_in"))
      (node (ref "U30") (pin "4") (pinfunction "GND_4") (pintype "power_in"))
      (node (ref "U31") (pin "4") (pinfunction "GND_4") (pintype "power_in"))
      (node (ref "U32") (pin "4") (pinfunction "GND_4") (pintype "power_in"))
      (node (ref "U33") (pin "4") (pinfunction "GND_4") (pintype "power_in"))
      (node (ref "U34") (pin "4") (pinfunction "GND_4") (pintype "power_in"))
      (node (ref "U35") (pin "4") (pinfunction "GND_4") (pintype "power_in"))
      (node (ref "U36") (pin "4") (pinfunction "GND_4") (pintype "power_in"))
      (node (ref "U37") (pin "4") (pinfunction "GND_4") (pintype "power_in"))
      (node (ref "U38") (pin "4") (pinfunction "GND_4") (pintype "power_in"))
      (node (ref "U39") (pin "4") (pinfunction "GND_4") (pintype "power_in"))
      (node (ref "U4") (pin "4") (pinfunction "GND_4") (pintype "power_in"))
      (node (ref "U40") (pin "4") (pinfunction "GND_4") (pintype "power_in"))
      (node (ref "U41") (pin "4") (pinfunction "GND_4") (pintype "power_in"))
      (node (ref "U42") (pin "4") (pinfunction "GND_4") (pintype "power_in"))
      (node (ref "U43") (pin "CASE1") (pinfunction "CASE_CASE1") (pintype "bidirectional"))
      (node (ref "U43") (pin "CASE2") (pinfunction "CASE_CASE2") (pintype "bidirectional"))
      (node (ref "U44") (pin "CASE1") (pinfunction "CASE_CASE1") (pintype "bidirectional"))
      (node (ref "U44") (pin "CASE2") (pinfunction "CASE_CASE2") (pintype "bidirectional"))
      (node (ref "U45") (pin "CASE1") (pinfunction "CASE_CASE1") (pintype "bidirectional"))
      (node (ref "U45") (pin "CASE2") (pinfunction "CASE_CASE2") (pintype "bidirectional"))
      (node (ref "U46") (pin "CASE1") (pinfunction "CASE_CASE1") (pintype "bidirectional"))
      (node (ref "U46") (pin "CASE2") (pinfunction "CASE_CASE2") (pintype "bidirectional"))
      (node (ref "U47") (pin "B5") (pinfunction "GND_B5") (pintype "power_in"))
      (node (ref "U47") (pin "C1") (pinfunction "GND_C1") (pintype "power_in"))
      (node (ref "U47") (pin "C2") (pinfunction "GND_C2") (pintype "power_in"))
      (node (ref "U47") (pin "C5") (pinfunction "SYNC/MODE_C5") (pintype "input"))
      (node (ref "U47") (pin "D5") (pinfunction "GND_D5") (pintype "power_in"))
      (node (ref "U48") (pin "4") (pinfunction "AGND_4") (pintype "bidirectional"))
      (node (ref "U49") (pin "GND@1") (pinfunction "GND_GND@1") (pintype "power_in"))
      (node (ref "U49") (pin "GND@2") (pinfunction "GND_GND@2") (pintype "power_in"))
      (node (ref "U5") (pin "4") (pinfunction "GND_4") (pintype "power_in"))
      (node (ref "U50") (pin "12") (pinfunction "GND_12") (pintype "bidirectional"))
      (node (ref "U50") (pin "2") (pinfunction "A1_2") (pintype "bidirectional"))
      (node (ref "U50") (pin "21") (pinfunction "A0_21") (pintype "bidirectional"))
      (node (ref "U50") (pin "3") (pinfunction "A2_3") (pintype "bidirectional"))
      (node (ref "U51") (pin "10") (pinfunction "C+_10") (pintype "input"))
      (node (ref "U51") (pin "12") (pinfunction "~{EN}_12") (pintype "input"))
      (node (ref "U51") (pin "14") (pinfunction "D+_14") (pintype "input"))
      (node (ref "U51") (pin "15") (pinfunction "D-_15") (pintype "input"))
      (node (ref "U51") (pin "8") (pinfunction "GND_8") (pintype "power_in"))
      (node (ref "U51") (pin "9") (pinfunction "C-_9") (pintype "input"))
      (node (ref "U52") (pin "4") (pinfunction "GND_4") (pintype "power_in"))
      (node (ref "U52") (pin "PAD") (pinfunction "GND_PAD") (pintype "power_in"))
      (node (ref "U53") (pin "3") (pinfunction "BIN_3") (pintype "input"))
      (node (ref "U53") (pin "4") (pinfunction "GND_4") (pintype "power_in"))
      (node (ref "U53") (pin "PAD") (pinfunction "GND_PAD") (pintype "power_in"))
      (node (ref "U6") (pin "4") (pinfunction "GND_4") (pintype "power_in"))
      (node (ref "U7") (pin "4") (pinfunction "GND_4") (pintype "power_in"))
      (node (ref "U8") (pin "4") (pinfunction "GND_4") (pintype "power_in"))
      (node (ref "U9") (pin "4") (pinfunction "GND_4") (pintype "power_in"))
    )
    (net (code "69") (name "HARP_CLKOUT") (class "Default")
      (node (ref "U48") (pin "2") (pinfunction "A1_2") (pintype "bidirectional"))
      (node (ref "U49") (pin "24") (pinfunction "24_24") (pintype "bidirectional"))
    )
    (net (code "70") (name "I2C_SCL") (class "Default")
      (node (ref "R23") (pin "2") (pinfunction "2_2") (pintype "passive"))
      (node (ref "U49") (pin "23") (pinfunction "23_23") (pintype "bidirectional"))
      (node (ref "U50") (pin "22") (pinfunction "SCL_22") (pintype "bidirectional"))
    )
    (net (code "71") (name "I2C_SDA") (class "Default")
      (node (ref "R24") (pin "2") (pinfunction "2_2") (pintype "passive"))
      (node (ref "U49") (pin "22") (pinfunction "22_22") (pintype "bidirectional"))
      (node (ref "U50") (pin "23") (pinfunction "SDA_23") (pintype "bidirectional"))
    )
    (net (code "72") (name "LVDS_IN_0") (class "Default")
      (node (ref "U49") (pin "18") (pinfunction "18_18") (pintype "bidirectional"))
      (node (ref "U51") (pin "3") (pinfunction "AOUT_3") (pintype "output"))
    )
    (net (code "73") (name "LVDS_IN_1") (class "Default")
      (node (ref "U49") (pin "17") (pinfunction "17_17") (pintype "bidirectional"))
      (node (ref "U51") (pin "5") (pinfunction "BOUT_5") (pintype "output"))
    )
    (net (code "74") (name "LVDS_OUT_0") (class "Default")
      (node (ref "U49") (pin "19") (pinfunction "19_19") (pintype "bidirectional"))
      (node (ref "U52") (pin "3") (pinfunction "BIN_3") (pintype "input"))
    )
    (net (code "75") (name "LVDS_OUT_1") (class "Default")
      (node (ref "U49") (pin "20") (pinfunction "20_20") (pintype "bidirectional"))
      (node (ref "U52") (pin "2") (pinfunction "AIN_2") (pintype "input"))
    )
    (net (code "76") (name "LVDS_OUT_2") (class "Default")
      (node (ref "U49") (pin "21") (pinfunction "21_21") (pintype "bidirectional"))
      (node (ref "U53") (pin "2") (pinfunction "AIN_2") (pintype "input"))
    )
    (net (code "77") (name "NEOPIXEL_DIN") (class "Default")
      (node (ref "J30") (pin "1") (pinfunction "1_1") (pintype "passive"))
      (node (ref "U10") (pin "3") (pinfunction "A_3") (pintype "bidirectional"))
    )
    (net (code "78") (name "Net-(C32-Pad1)") (class "Default")
      (node (ref "C32") (pin "1") (pinfunction "1_1") (pintype "passive"))
      (node (ref "R7") (pin "1") (pinfunction "1_1") (pintype "passive"))
    )
    (net (code "79") (name "Net-(C33-Pad1)") (class "Default")
      (node (ref "C33") (pin "1") (pinfunction "1_1") (pintype "passive"))
      (node (ref "R8") (pin "1") (pinfunction "1_1") (pintype "passive"))
    )
    (net (code "80") (name "Net-(C34-Pad1)") (class "Default")
      (node (ref "C34") (pin "1") (pinfunction "1_1") (pintype "passive"))
      (node (ref "R9") (pin "1") (pinfunction "1_1") (pintype "passive"))
    )
    (net (code "81") (name "Net-(C35-Pad1)") (class "Default")
      (node (ref "C35") (pin "1") (pinfunction "1_1") (pintype "passive"))
      (node (ref "R10") (pin "1") (pinfunction "1_1") (pintype "passive"))
    )
    (net (code "82") (name "Net-(J1-1)") (class "Default")
      (node (ref "J1") (pin "CLK") (pinfunction "1_CLK") (pintype "passive"))
      (node (ref "U43") (pin "1X6") (pinfunction "COM_A_1X6") (pintype "bidirectional"))
    )
    (net (code "83") (name "Net-(J2-1)") (class "Default")
      (node (ref "J2") (pin "CLK") (pinfunction "1_CLK") (pintype "passive"))
      (node (ref "U44") (pin "1X6") (pinfunction "COM_A_1X6") (pintype "bidirectional"))
    )
    (net (code "84") (name "Net-(J3-1)") (class "Default")
      (node (ref "J3") (pin "CLK") (pinfunction "1_CLK") (pintype "passive"))
      (node (ref "U45") (pin "1X6") (pinfunction "COM_A_1X6") (pintype "bidirectional"))
    )
    (net (code "85") (name "Net-(J4-1)") (class "Default")
      (node (ref "J4") (pin "CLK") (pinfunction "1_CLK") (pintype "passive"))
      (node (ref "U46") (pin "1X6") (pinfunction "COM_A_1X6") (pintype "bidirectional"))
    )
    (net (code "86") (name "Net-(J5-1)") (class "Default")
      (node (ref "J5") (pin "SIG") (pinfunction "1_SIG") (pintype "passive"))
      (node (ref "U43") (pin "5") (pinfunction "NO_A_5") (pintype "bidirectional"))
    )
    (net (code "87") (name "Net-(J6-1)") (class "Default")
      (node (ref "J6") (pin "SIG") (pinfunction "1_SIG") (pintype "passive"))
      (node (ref "U44") (pin "5") (pinfunction "NO_A_5") (pintype "bidirectional"))
    )
    (net (code "88") (name "Net-(J7-1)") (class "Default")
      (node (ref "J7") (pin "SIG") (pinfunction "1_SIG") (pintype "passive"))
      (node (ref "U45") (pin "5") (pinfunction "NO_A_5") (pintype "bidirectional"))
    )
    (net (code "89") (name "Net-(J8-1)") (class "Default")
      (node (ref "J8") (pin "SIG") (pinfunction "1_SIG") (pintype "passive"))
      (node (ref "U46") (pin "5") (pinfunction "NO_A_5") (pintype "bidirectional"))
    )
    (net (code "90") (name "Net-(J15-1)") (class "Default")
      (node (ref "J15") (pin "SIG") (pinfunction "1_SIG") (pintype "passive"))
      (node (ref "J16") (pin "CLK") (pinfunction "1_CLK") (pintype "passive"))
    )
    (net (code "91") (name "Net-(J18-1)") (class "Default")
      (node (ref "J18") (pin "SIG") (pinfunction "1_SIG") (pintype "passive"))
      (node (ref "J19") (pin "CLK") (pinfunction "1_CLK") (pintype "passive"))
    )
    (net (code "92") (name "Net-(J27-1)") (class "Default")
      (node (ref "J27") (pin "SIG") (pinfunction "1_SIG") (pintype "passive"))
      (node (ref "J28") (pin "CLK") (pinfunction "1_CLK") (pintype "passive"))
    )
    (net (code "93") (name "Net-(Q1-D)") (class "Default")
      (node (ref "D1") (pin "A") (pinfunction "A_A") (pintype "passive"))
      (node (ref "Q1") (pin "3") (pinfunction "D_3") (pintype "bidirectional"))
      (node (ref "U43") (pin "7") (pinfunction "COIL-_7") (pintype "bidirectional"))
    )
    (net (code "94") (name "Net-(Q1-S)") (class "Default")
      (node (ref "Q1") (pin "2") (pinfunction "S_2") (pintype "bidirectional"))
      (node (ref "Q5") (pin "3") (pinfunction "D_3") (pintype "bidirectional"))
    )
    (net (code "95") (name "Net-(Q2-D)") (class "Default")
      (node (ref "D2") (pin "A") (pinfunction "A_A") (pintype "passive"))
      (node (ref "Q2") (pin "3") (pinfunction "D_3") (pintype "bidirectional"))
      (node (ref "U44") (pin "7") (pinfunction "COIL-_7") (pintype "bidirectional"))
    )
    (net (code "96") (name "Net-(Q2-S)") (class "Default")
      (node (ref "Q2") (pin "2") (pinfunction "S_2") (pintype "bidirectional"))
      (node (ref "Q6") (pin "3") (pinfunction "D_3") (pintype "bidirectional"))
    )
    (net (code "97") (name "Net-(Q3-D)") (class "Default")
      (node (ref "D3") (pin "A") (pinfunction "A_A") (pintype "passive"))
      (node (ref "Q3") (pin "3") (pinfunction "D_3") (pintype "bidirectional"))
      (node (ref "U45") (pin "7") (pinfunction "COIL-_7") (pintype "bidirectional"))
    )
    (net (code "98") (name "Net-(Q3-S)") (class "Default")
      (node (ref "Q3") (pin "2") (pinfunction "S_2") (pintype "bidirectional"))
      (node (ref "Q7") (pin "3") (pinfunction "D_3") (pintype "bidirectional"))
    )
    (net (code "99") (name "Net-(Q4-D)") (class "Default")
      (node (ref "D4") (pin "A") (pinfunction "A_A") (pintype "passive"))
      (node (ref "Q4") (pin "3") (pinfunction "D_3") (pintype "bidirectional"))
      (node (ref "U46") (pin "7") (pinfunction "COIL-_7") (pintype "bidirectional"))
    )
    (net (code "100") (name "Net-(Q4-S)") (class "Default")
      (node (ref "Q4") (pin "2") (pinfunction "S_2") (pintype "bidirectional"))
      (node (ref "Q8") (pin "3") (pinfunction "D_3") (pintype "bidirectional"))
    )
    (net (code "101") (name "Net-(Q9-PadS)") (class "Default")
      (node (ref "Q9") (pin "S") (pinfunction "S_S") (pintype "bidirectional"))
      (node (ref "U49") (pin "VIN") (pinfunction "VIN_VIN") (pintype "power_in"))
    )
    (net (code "102") (name "Net-(S1-2)") (class "Default")
      (node (ref "R3") (pin "1") (pinfunction "1_1") (pintype "passive"))
      (node (ref "S1") (pin "1") (pinfunction "2_1") (pintype "passive"))
    )
    (net (code "103") (name "Net-(S2-2)") (class "Default")
      (node (ref "R4") (pin "2") (pinfunction "2_2") (pintype "passive"))
      (node (ref "S2") (pin "1") (pinfunction "2_1") (pintype "passive"))
    )
    (net (code "104") (name "Net-(S3-2)") (class "Default")
      (node (ref "R5") (pin "2") (pinfunction "2_2") (pintype "passive"))
      (node (ref "S3") (pin "1") (pinfunction "2_1") (pintype "passive"))
    )
    (net (code "105") (name "Net-(S4-2)") (class "Default")
      (node (ref "R6") (pin "2") (pinfunction "2_2") (pintype "passive"))
      (node (ref "S4") (pin "1") (pinfunction "2_1") (pintype "passive"))
    )
    (net (code "106") (name "Net-(U1-DIN)") (class "Default")
      (node (ref "R1") (pin "2") (pinfunction "2_2") (pintype "passive"))
      (node (ref "U1") (pin "1") (pinfunction "DIN_1") (pintype "input"))
    )
    (net (code "107") (name "Net-(U1-DOUT)") (class "Default")
      (node (ref "U1") (pin "3") (pinfunction "DOUT_3") (pintype "output"))
      (node (ref "U2") (pin "1") (pinfunction "DIN_1") (pintype "input"))
    )
    (net (code "108") (name "Net-(U2-DOUT)") (class "Default")
      (node (ref "U2") (pin "3") (pinfunction "DOUT_3") (pintype "output"))
      (node (ref "U3") (pin "1") (pinfunction "DIN_1") (pintype "input"))
    )
    (net (code "109") (name "Net-(U3-DOUT)") (class "Default")
      (node (ref "U3") (pin "3") (pinfunction "DOUT_3") (pintype "output"))
      (node (ref "U4") (pin "1") (pinfunction "DIN_1") (pintype "input"))
    )
    (net (code "110") (name "Net-(U4-DOUT)") (class "Default")
      (node (ref "U4") (pin "3") (pinfunction "DOUT_3") (pintype "output"))
      (node (ref "U5") (pin "1") (pinfunction "DIN_1") (pintype "input"))
    )
    (net (code "111") (name "Net-(U5-DOUT)") (class "Default")
      (node (ref "U5") (pin "3") (pinfunction "DOUT_3") (pintype "output"))
      (node (ref "U6") (pin "1") (pinfunction "DIN_1") (pintype "input"))
    )
    (net (code "112") (name "Net-(U6-DOUT)") (class "Default")
      (node (ref "U6") (pin "3") (pinfunction "DOUT_3") (pintype "output"))
      (node (ref "U7") (pin "1") (pinfunction "DIN_1") (pintype "input"))
    )
    (net (code "113") (name "Net-(U7-DOUT)") (class "Default")
      (node (ref "U7") (pin "3") (pinfunction "DOUT_3") (pintype "output"))
      (node (ref "U8") (pin "1") (pinfunction "DIN_1") (pintype "input"))
    )
    (net (code "114") (name "Net-(U8-DOUT)") (class "Default")
      (node (ref "U8") (pin "3") (pinfunction "DOUT_3") (pintype "output"))
      (node (ref "U9") (pin "1") (pinfunction "DIN_1") (pintype "input"))
    )
    (net (code "115") (name "Net-(U10-B)") (class "Default")
      (node (ref "R1") (pin "1") (pinfunction "1_1") (pintype "passive"))
      (node (ref "U10") (pin "4") (pinfunction "B_4") (pintype "bidirectional"))
    )
    (net (code "116") (name "Net-(U10-OE)") (class "Default")
      (node (ref "R2") (pin "2") (pinfunction "2_2") (pintype "passive"))
      (node (ref "U10") (pin "5") (pinfunction "OE_5") (pintype "bidirectional"))
    )
    (net (code "117") (name "Net-(U11-DIN)") (class "Default")
      (node (ref "U11") (pin "1") (pinfunction "DIN_1") (pintype "input"))
      (node (ref "U9") (pin "3") (pinfunction "DOUT_3") (pintype "output"))
    )
    (net (code "118") (name "Net-(U11-DOUT)") (class "Default")
      (node (ref "U11") (pin "3") (pinfunction "DOUT_3") (pintype "output"))
      (node (ref "U12") (pin "1") (pinfunction "DIN_1") (pintype "input"))
    )
    (net (code "119") (name "Net-(U12-DOUT)") (class "Default")
      (node (ref "U12") (pin "3") (pinfunction "DOUT_3") (pintype "output"))
      (node (ref "U13") (pin "1") (pinfunction "DIN_1") (pintype "input"))
    )
    (net (code "120") (name "Net-(U13-DOUT)") (class "Default")
      (node (ref "U13") (pin "3") (pinfunction "DOUT_3") (pintype "output"))
      (node (ref "U14") (pin "1") (pinfunction "DIN_1") (pintype "input"))
    )
    (net (code "121") (name "Net-(U14-DOUT)") (class "Default")
      (node (ref "U14") (pin "3") (pinfunction "DOUT_3") (pintype "output"))
      (node (ref "U15") (pin "1") (pinfunction "DIN_1") (pintype "input"))
    )
    (net (code "122") (name "Net-(U15-DOUT)") (class "Default")
      (node (ref "U15") (pin "3") (pinfunction "DOUT_3") (pintype "output"))
      (node (ref "U16") (pin "1") (pinfunction "DIN_1") (pintype "input"))
    )
    (net (code "123") (name "Net-(U16-DOUT)") (class "Default")
      (node (ref "U16") (pin "3") (pinfunction "DOUT_3") (pintype "output"))
      (node (ref "U17") (pin "1") (pinfunction "DIN_1") (pintype "input"))
    )
    (net (code "124") (name "Net-(U17-DOUT)") (class "Default")
      (node (ref "U17") (pin "3") (pinfunction "DOUT_3") (pintype "output"))
      (node (ref "U18") (pin "1") (pinfunction "DIN_1") (pintype "input"))
    )
    (net (code "125") (name "Net-(U18-DOUT)") (class "Default")
      (node (ref "U18") (pin "3") (pinfunction "DOUT_3") (pintype "output"))
      (node (ref "U19") (pin "1") (pinfunction "DIN_1") (pintype "input"))
    )
    (net (code "126") (name "Net-(U19-DOUT)") (class "Default")
      (node (ref "U19") (pin "3") (pinfunction "DOUT_3") (pintype "output"))
      (node (ref "U20") (pin "1") (pinfunction "DIN_1") (pintype "input"))
    )
    (net (code "127") (name "Net-(U20-DOUT)") (class "Default")
      (node (ref "U20") (pin "3") (pinfunction "DOUT_3") (pintype "output"))
      (node (ref "U21") (pin "1") (pinfunction "DIN_1") (pintype "input"))
    )
    (net (code "128") (name "Net-(U21-DOUT)") (class "Default")
      (node (ref "U21") (pin "3") (pinfunction "DOUT_3") (pintype "output"))
      (node (ref "U22") (pin "1") (pinfunction "DIN_1") (pintype "input"))
    )
    (net (code "129") (name "Net-(U22-DOUT)") (class "Default")
      (node (ref "U22") (pin "3") (pinfunction "DOUT_3") (pintype "output"))
      (node (ref "U23") (pin "1") (pinfunction "DIN_1") (pintype "input"))
    )
    (net (code "130") (name "Net-(U23-DOUT)") (class "Default")
      (node (ref "U23") (pin "3") (pinfunction "DOUT_3") (pintype "output"))
      (node (ref "U24") (pin "1") (pinfunction "DIN_1") (pintype "input"))
    )
    (net (code "131") (name "Net-(U24-DOUT)") (class "Default")
      (node (ref "U24") (pin "3") (pinfunction "DOUT_3") (pintype "output"))
      (node (ref "U25") (pin "1") (pinfunction "DIN_1") (pintype "input"))
    )
    (net (code "132") (name "Net-(U25-DOUT)") (class "Default")
      (node (ref "U25") (pin "3") (pinfunction "DOUT_3") (pintype "output"))
      (node (ref "U26") (pin "1") (pinfunction "DIN_1") (pintype "input"))
    )
    (net (code "133") (name "Net-(U26-DOUT)") (class "Default")
      (node (ref "U26") (pin "3") (pinfunction "DOUT_3") (pintype "output"))
      (node (ref "U27") (pin "1") (pinfunction "DIN_1") (pintype "input"))
    )
    (net (code "134") (name "Net-(U27-DOUT)") (class "Default")
      (node (ref "U27") (pin "3") (pinfunction "DOUT_3") (pintype "output"))
      (node (ref "U28") (pin "1") (pinfunction "DIN_1") (pintype "input"))
    )
    (net (code "135") (name "Net-(U28-DOUT)") (class "Default")
      (node (ref "U28") (pin "3") (pinfunction "DOUT_3") (pintype "output"))
      (node (ref "U29") (pin "1") (pinfunction "DIN_1") (pintype "input"))
    )
    (net (code "136") (name "Net-(U29-DOUT)") (class "Default")
      (node (ref "U29") (pin "3") (pinfunction "DOUT_3") (pintype "output"))
      (node (ref "U30") (pin "1") (pinfunction "DIN_1") (pintype "input"))
    )
    (net (code "137") (name "Net-(U30-DOUT)") (class "Default")
      (node (ref "U30") (pin "3") (pinfunction "DOUT_3") (pintype "output"))
      (node (ref "U31") (pin "1") (pinfunction "DIN_1") (pintype "input"))
    )
    (net (code "138") (name "Net-(U31-DOUT)") (class "Default")
      (node (ref "U31") (pin "3") (pinfunction "DOUT_3") (pintype "output"))
      (node (ref "U32") (pin "1") (pinfunction "DIN_1") (pintype "input"))
    )
    (net (code "139") (name "Net-(U32-DOUT)") (class "Default")
      (node (ref "U32") (pin "3") (pinfunction "DOUT_3") (pintype "output"))
      (node (ref "U33") (pin "1") (pinfunction "DIN_1") (pintype "input"))
    )
    (net (code "140") (name "Net-(U33-DOUT)") (class "Default")
      (node (ref "U33") (pin "3") (pinfunction "DOUT_3") (pintype "output"))
      (node (ref "U34") (pin "1") (pinfunction "DIN_1") (pintype "input"))
    )
    (net (code "141") (name "Net-(U34-DOUT)") (class "Default")
      (node (ref "U34") (pin "3") (pinfunction "DOUT_3") (pintype "output"))
      (node (ref "U35") (pin "1") (pinfunction "DIN_1") (pintype "input"))
    )
    (net (code "142") (name "Net-(U35-DOUT)") (class "Default")
      (node (ref "U35") (pin "3") (pinfunction "DOUT_3") (pintype "output"))
      (node (ref "U36") (pin "1") (pinfunction "DIN_1") (pintype "input"))
    )
    (net (code "143") (name "Net-(U36-DOUT)") (class "Default")
      (node (ref "U36") (pin "3") (pinfunction "DOUT_3") (pintype "output"))
      (node (ref "U37") (pin "1") (pinfunction "DIN_1") (pintype "input"))
    )
    (net (code "144") (name "Net-(U37-DOUT)") (class "Default")
      (node (ref "U37") (pin "3") (pinfunction "DOUT_3") (pintype "output"))
      (node (ref "U38") (pin "1") (pinfunction "DIN_1") (pintype "input"))
    )
    (net (code "145") (name "Net-(U38-DOUT)") (class "Default")
      (node (ref "U38") (pin "3") (pinfunction "DOUT_3") (pintype "output"))
      (node (ref "U39") (pin "1") (pinfunction "DIN_1") (pintype "input"))
    )
    (net (code "146") (name "Net-(U39-DOUT)") (class "Default")
      (node (ref "U39") (pin "3") (pinfunction "DOUT_3") (pintype "output"))
      (node (ref "U40") (pin "1") (pinfunction "DIN_1") (pintype "input"))
    )
    (net (code "147") (name "Net-(U40-DOUT)") (class "Default")
      (node (ref "U40") (pin "3") (pinfunction "DOUT_3") (pintype "output"))
      (node (ref "U41") (pin "1") (pinfunction "DIN_1") (pintype "input"))
    )
    (net (code "148") (name "Net-(U41-DOUT)") (class "Default")
      (node (ref "U41") (pin "3") (pinfunction "DOUT_3") (pintype "output"))
      (node (ref "U42") (pin "1") (pinfunction "DIN_1") (pintype "input"))
    )
    (net (code "149") (name "Net-(U43-NC_A)") (class "Default")
      (node (ref "C32") (pin "2") (pinfunction "2_2") (pintype "passive"))
      (node (ref "U43") (pin "6") (pinfunction "NC_A_6") (pintype "bidirectional"))
    )
    (net (code "150") (name "Net-(U44-NC_A)") (class "Default")
      (node (ref "C33") (pin "2") (pinfunction "2_2") (pintype "passive"))
      (node (ref "U44") (pin "6") (pinfunction "NC_A_6") (pintype "bidirectional"))
    )
    (net (code "151") (name "Net-(U45-NC_A)") (class "Default")
      (node (ref "C34") (pin "2") (pinfunction "2_2") (pintype "passive"))
      (node (ref "U45") (pin "6") (pinfunction "NC_A_6") (pintype "bidirectional"))
    )
    (net (code "152") (name "Net-(U46-NC_A)") (class "Default")
      (node (ref "C35") (pin "2") (pinfunction "2_2") (pintype "passive"))
      (node (ref "U46") (pin "6") (pinfunction "NC_A_6") (pintype "bidirectional"))
    )
    (net (code "153") (name "Net-(U47-FB1)") (class "Default")
      (node (ref "R19") (pin "1") (pinfunction "1_1") (pintype "passive"))
      (node (ref "U47") (pin "E4") (pinfunction "FB1_E4") (pintype "input"))
    )
    (net (code "154") (name "Net-(U47-FB2)") (class "Default")
      (node (ref "R21") (pin "1") (pinfunction "1_1") (pintype "passive"))
      (node (ref "U47") (pin "A4") (pinfunction "FB2_A4") (pintype "input"))
    )
    (net (code "155") (name "Net-(U47-FREQ)") (class "Default")
      (node (ref "R20") (pin "1") (pinfunction "1_1") (pintype "passive"))
      (node (ref "U47") (pin "C4") (pinfunction "FREQ_C4") (pintype "input"))
    )
    (net (code "156") (name "Net-(U47-TRACK{slash}SS1)") (class "Default")
      (node (ref "C39") (pin "2") (pinfunction "2_2") (pintype "passive"))
      (node (ref "U47") (pin "E3") (pinfunction "TRACK/SS1_E3") (pintype "input"))
    )
    (net (code "157") (name "Net-(U47-TRACK{slash}SS2)") (class "Default")
      (node (ref "C38") (pin "2") (pinfunction "2_2") (pintype "passive"))
      (node (ref "U47") (pin "A3") (pinfunction "TRACK/SS2_A3") (pintype "input"))
    )
    (net (code "158") (name "Net-(U48-B1)") (class "Default")
      (node (ref "J29") (pin "4") (pinfunction "4_4") (pintype "passive"))
      (node (ref "U48") (pin "6") (pinfunction "B1_6") (pintype "bidirectional"))
    )
    (net (code "159") (name "Net-(U48-BGND)") (class "Default")
      (node (ref "C41") (pin "2") (pinfunction "2_2") (pintype "passive"))
      (node (ref "J29") (pin "5") (pinfunction "5_5") (pintype "passive"))
      (node (ref "U48") (pin "5") (pinfunction "BGND_5") (pintype "bidirectional"))
    )
    (net (code "160") (name "Net-(U48-BVDD)") (class "Default")
      (node (ref "C41") (pin "1") (pinfunction "1_1") (pintype "passive"))
      (node (ref "J29") (pin "1") (pinfunction "1_1") (pintype "passive"))
      (node (ref "U48") (pin "8") (pinfunction "BVDD_8") (pintype "bidirectional"))
    )
    (net (code "161") (name "RELAY_AND_0") (class "Default")
      (node (ref "Q5") (pin "1") (pinfunction "G_1") (pintype "bidirectional"))
      (node (ref "R11") (pin "2") (pinfunction "2_2") (pintype "passive"))
      (node (ref "U50") (pin "8") (pinfunction "P04_8") (pintype "bidirectional"))
    )
    (net (code "162") (name "RELAY_AND_1") (class "Default")
      (node (ref "Q6") (pin "1") (pinfunction "G_1") (pintype "bidirectional"))
      (node (ref "R13") (pin "2") (pinfunction "2_2") (pintype "passive"))
      (node (ref "U50") (pin "6") (pinfunction "P02_6") (pintype "bidirectional"))
    )
    (net (code "163") (name "RELAY_AND_2") (class "Default")
      (node (ref "Q7") (pin "1") (pinfunction "G_1") (pintype "bidirectional"))
      (node (ref "R15") (pin "2") (pinfunction "2_2") (pintype "passive"))
      (node (ref "U50") (pin "4") (pinfunction "P00_4") (pintype "bidirectional"))
    )
    (net (code "164") (name "RELAY_AND_3") (class "Default")
      (node (ref "Q8") (pin "1") (pinfunction "G_1") (pintype "bidirectional"))
      (node (ref "R17") (pin "2") (pinfunction "2_2") (pintype "passive"))
      (node (ref "U50") (pin "20") (pinfunction "P17_20") (pintype "bidirectional"))
    )
    (net (code "165") (name "RELAY_MECH_0") (class "Default")
      (node (ref "C28") (pin "2") (pinfunction "2_2") (pintype "passive"))
      (node (ref "Q1") (pin "1") (pinfunction "G_1") (pintype "bidirectional"))
      (node (ref "R12") (pin "2") (pinfunction "2_2") (pintype "passive"))
      (node (ref "R3") (pin "2") (pinfunction "2_2") (pintype "passive"))
      (node (ref "U50") (pin "9") (pinfunction "P05_9") (pintype "bidirectional"))
    )
    (net (code "166") (name "RELAY_MECH_1") (class "Default")
      (node (ref "C29") (pin "2") (pinfunction "2_2") (pintype "passive"))
      (node (ref "Q2") (pin "1") (pinfunction "G_1") (pintype "bidirectional"))
      (node (ref "R14") (pin "2") (pinfunction "2_2") (pintype "passive"))
      (node (ref "R4") (pin "1") (pinfunction "1_1") (pintype "passive"))
      (node (ref "U50") (pin "7") (pinfunction "P03_7") (pintype "bidirectional"))
    )
    (net (code "167") (name "RELAY_MECH_2") (class "Default")
      (node (ref "C30") (pin "2") (pinfunction "2_2") (pintype "passive"))
      (node (ref "Q3") (pin "1") (pinfunction "G_1") (pintype "bidirectional"))
      (node (ref "R16") (pin "2") (pinfunction "2_2") (pintype "passive"))
      (node (ref "R5") (pin "1") (pinfunction "1_1") (pintype "passive"))
      (node (ref "U50") (pin "5") (pinfunction "P01_5") (pintype "bidirectional"))
    )
    (net (code "168") (name "RELAY_MECH_3") (class "Default")
      (node (ref "C31") (pin "2") (pinfunction "2_2") (pintype "passive"))
      (node (ref "Q4") (pin "1") (pinfunction "G_1") (pintype "bidirectional"))
      (node (ref "R18") (pin "2") (pinfunction "2_2") (pintype "passive"))
      (node (ref "R6") (pin "1") (pinfunction "1_1") (pintype "passive"))
      (node (ref "U50") (pin "19") (pinfunction "P16_19") (pintype "bidirectional"))
    )
    (net (code "169") (name "unconnected-(U42-DOUT-Pad3)") (class "Default")
      (node (ref "U42") (pin "3") (pinfunction "DOUT_3") (pintype "output"))
    )
    (net (code "170") (name "unconnected-(U43-COM_B-Pad3)") (class "Default")
      (node (ref "U43") (pin "3") (pinfunction "COM_B_3") (pintype "bidirectional"))
    )
    (net (code "171") (name "unconnected-(U43-NC_B-Pad2)") (class "Default")
      (node (ref "U43") (pin "2") (pinfunction "NC_B_2") (pintype "bidirectional"))
    )
    (net (code "172") (name "unconnected-(U43-NO_B-Pad4)") (class "Default")
      (node (ref "U43") (pin "4") (pinfunction "NO_B_4") (pintype "bidirectional"))
    )
    (net (code "173") (name "unconnected-(U44-COM_B-Pad3)") (class "Default")
      (node (ref "U44") (pin "3") (pinfunction "COM_B_3") (pintype "bidirectional"))
    )
    (net (code "174") (name "unconnected-(U44-NC_B-Pad2)") (class "Default")
      (node (ref "U44") (pin "2") (pinfunction "NC_B_2") (pintype "bidirectional"))
    )
    (net (code "175") (name "unconnected-(U44-NO_B-Pad4)") (class "Default")
      (node (ref "U44") (pin "4") (pinfunction "NO_B_4") (pintype "bidirectional"))
    )
    (net (code "176") (name "unconnected-(U45-COM_B-Pad3)") (class "Default")
      (node (ref "U45") (pin "3") (pinfunction "COM_B_3") (pintype "bidirectional"))
    )
    (net (code "177") (name "unconnected-(U45-NC_B-Pad2)") (class "Default")
      (node (ref "U45") (pin "2") (pinfunction "NC_B_2") (pintype "bidirectional"))
    )
    (net (code "178") (name "unconnected-(U45-NO_B-Pad4)") (class "Default")
      (node (ref "U45") (pin "4") (pinfunction "NO_B_4") (pintype "bidirectional"))
    )
    (net (code "179") (name "unconnected-(U46-COM_B-Pad3)") (class "Default")
      (node (ref "U46") (pin "3") (pinfunction "COM_B_3") (pintype "bidirectional"))
    )
    (net (code "180") (name "unconnected-(U46-NC_B-Pad2)") (class "Default")
      (node (ref "U46") (pin "2") (pinfunction "NC_B_2") (pintype "bidirectional"))
    )
    (net (code "181") (name "unconnected-(U46-NO_B-Pad4)") (class "Default")
      (node (ref "U46") (pin "4") (pinfunction "NO_B_4") (pintype "bidirectional"))
    )
    (net (code "182") (name "unconnected-(U47-COMP1-PadE5)") (class "Default")
      (node (ref "U47") (pin "E5") (pinfunction "COMP1_E5") (pintype "bidirectional"))
    )
    (net (code "183") (name "unconnected-(U47-COMP2-PadA5)") (class "Default")
      (node (ref "U47") (pin "A5") (pinfunction "COMP2_A5") (pintype "bidirectional"))
    )
    (net (code "184") (name "unconnected-(U47-INTVCC-PadC3)") (class "Default")
      (node (ref "U47") (pin "C3") (pinfunction "INTVCC_C3") (pintype "output"))
    )
    (net (code "185") (name "unconnected-(U47-PGOOD1-PadD4)") (class "Default")
      (node (ref "U47") (pin "D4") (pinfunction "PGOOD1_D4") (pintype "open_collector"))
    )
    (net (code "186") (name "unconnected-(U48-AVDD{slash}NC-Pad3)") (class "Default")
      (node (ref "U48") (pin "3") (pinfunction "AVDD/NC_3") (pintype "bidirectional"))
    )
    (net (code "187") (name "unconnected-(U48-BGND{slash}NC-Pad7)") (class "Default")
      (node (ref "U48") (pin "7") (pinfunction "BGND/NC_7") (pintype "bidirectional"))
    )
    (net (code "188") (name "unconnected-(U50-P10-Pad13)") (class "Default")
      (node (ref "U50") (pin "13") (pinfunction "P10_13") (pintype "bidirectional"))
    )
    (net (code "189") (name "unconnected-(U50-P12-Pad15)") (class "Default")
      (node (ref "U50") (pin "15") (pinfunction "P12_15") (pintype "bidirectional"))
    )
    (net (code "190") (name "unconnected-(U51-COUT-Pad11)") (class "Default")
      (node (ref "U51") (pin "11") (pinfunction "COUT_11") (pintype "output"))
    )
    (net (code "191") (name "unconnected-(U51-DOUT-Pad13)") (class "Default")
      (node (ref "U51") (pin "13") (pinfunction "DOUT_13") (pintype "output"))
    )
    (net (code "192") (name "unconnected-(U53-BOUT+-Pad6)") (class "Default")
      (node (ref "U53") (pin "6") (pinfunction "BOUT+_6") (pintype "output"))
    )
    (net (code "193") (name "unconnected-(U53-BOUT--Pad5)") (class "Default")
      (node (ref "U53") (pin "5") (pinfunction "BOUT-_5") (pintype "output"))
    )
  )
)
